# FlightComputer_RevA.net
KiCad netlist of a schematic drawn in EAGLE
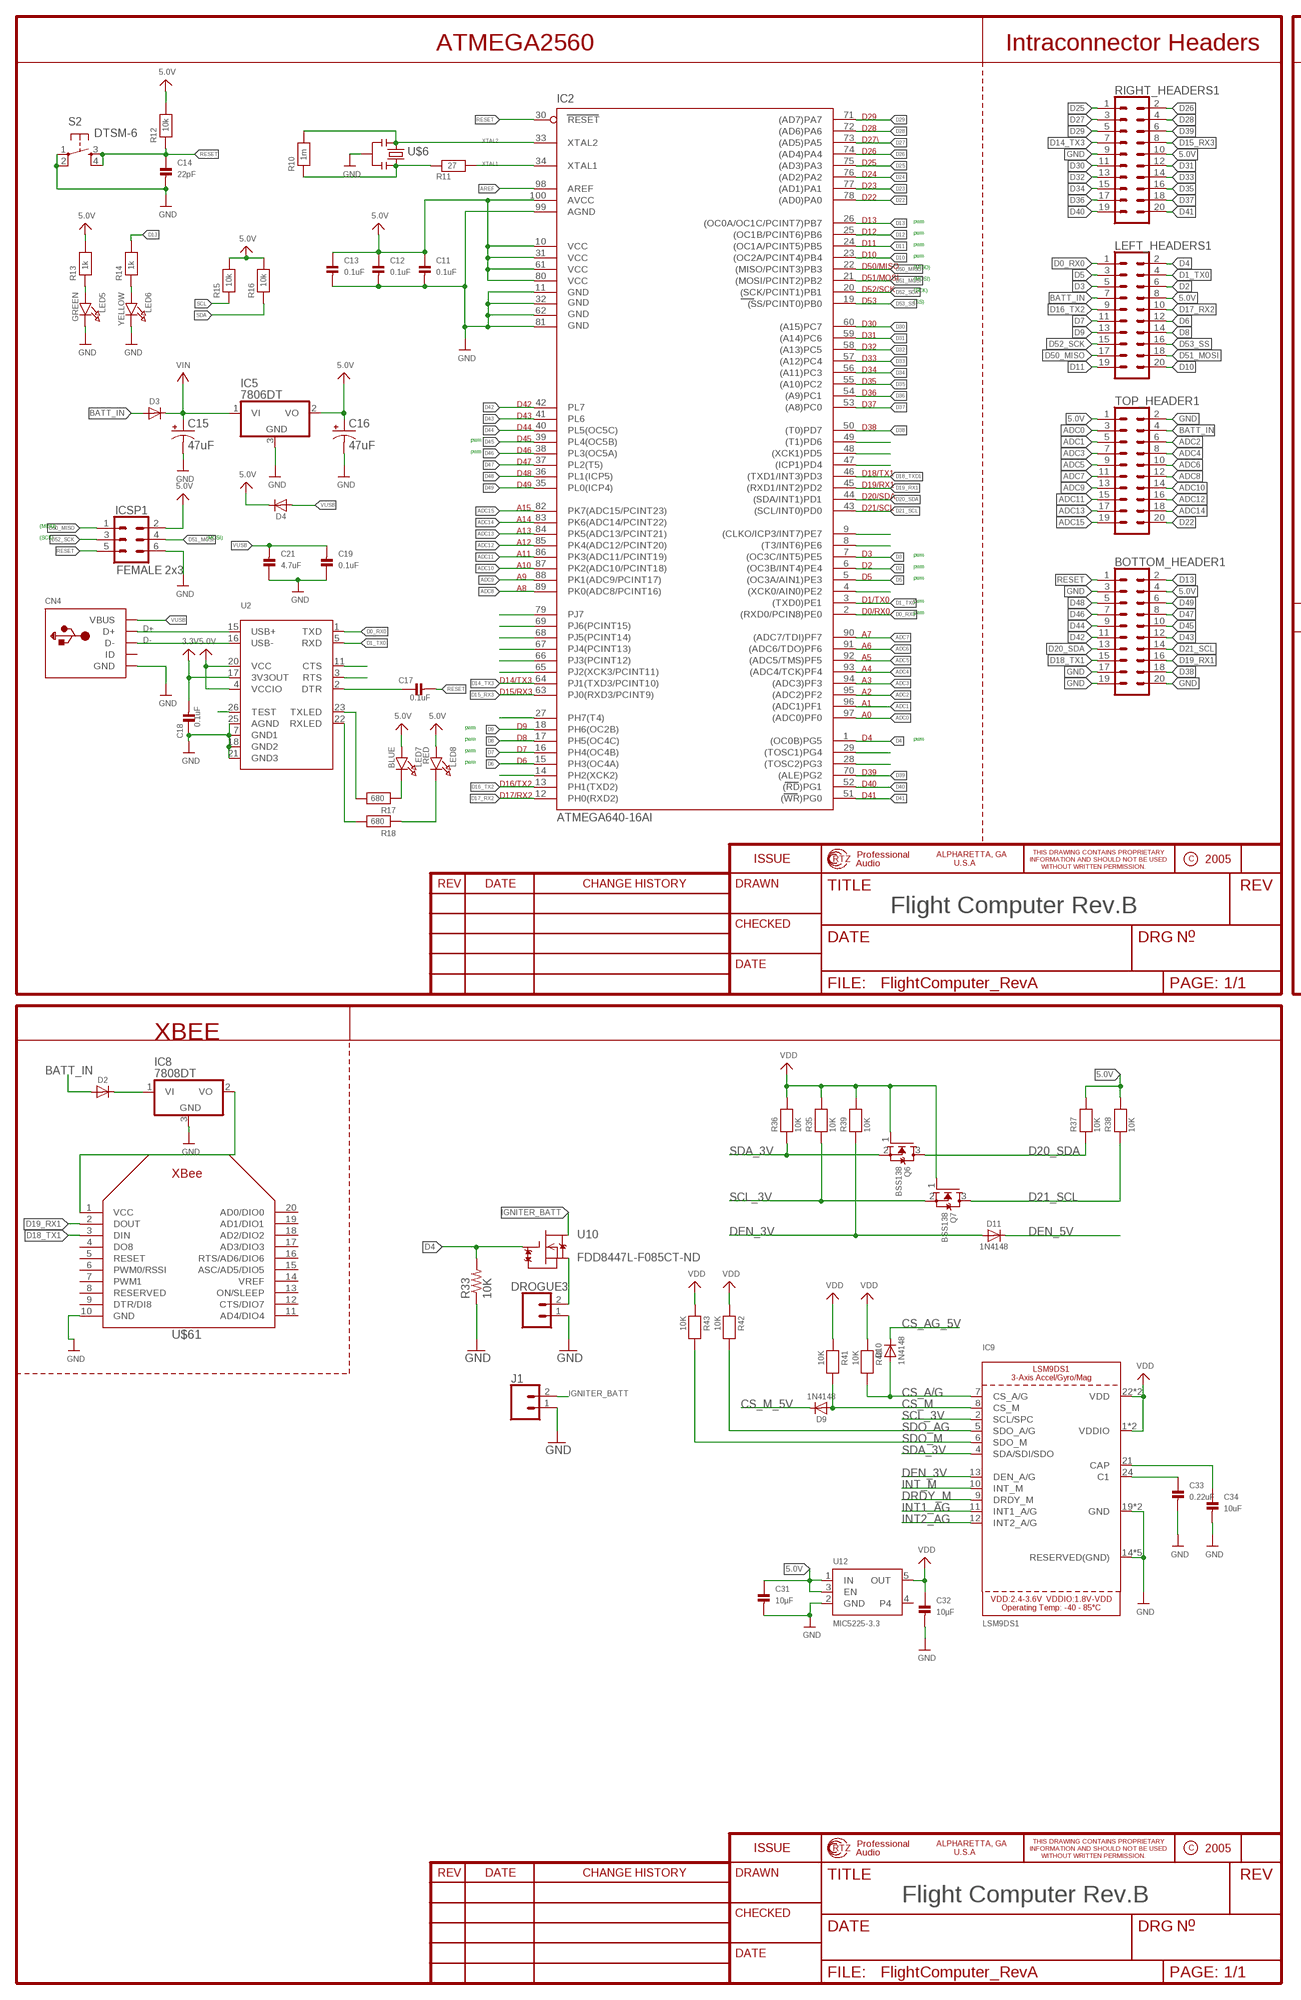
[diagram p0: schematic, sheet 1, part 1 of 2]
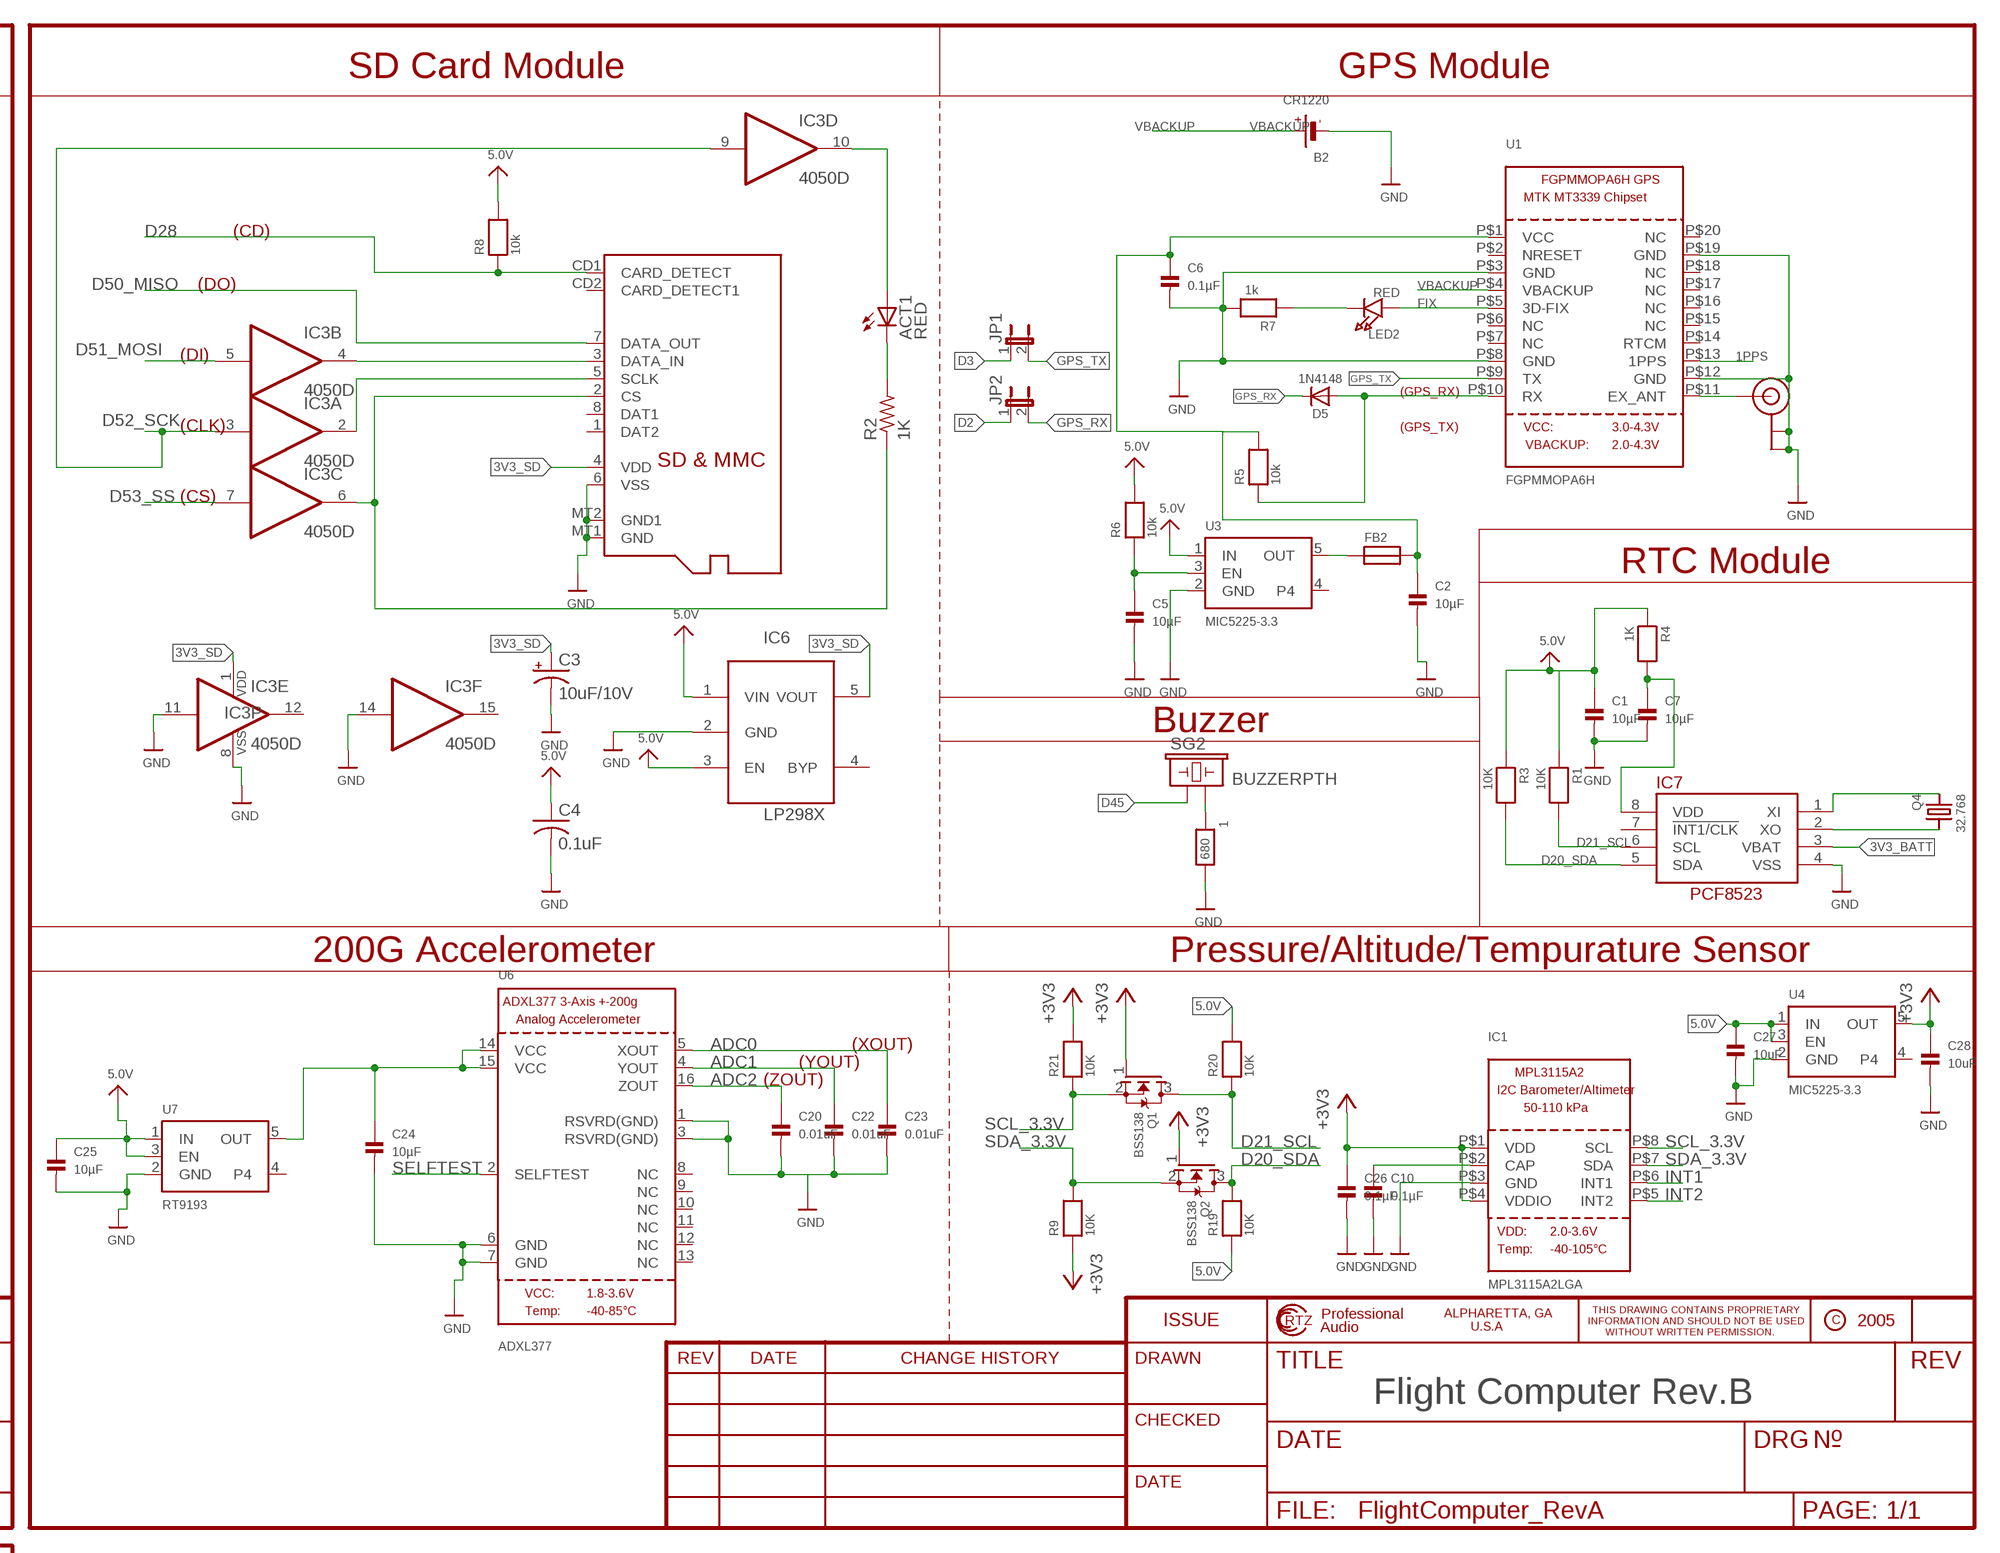
[diagram p1: schematic, sheet 1, part 2 of 2]

(export (version "E")
  (design (tool "Eeschema 10.0.6"))
  (components
    (comp (ref "1")
      (value "680")
      (footprint "eagle-import:0603")
      (libsource (lib "eagle-import") (part "RESISTOR0603"))
    )
    (comp (ref "ACT1")
      (value "RED")
      (footprint "eagle-import:CHIP-LED0805")
      (libsource (lib "eagle-import") (part "LEDCHIP-LED0805"))
    )
    (comp (ref "B2")
      (value "CR1220")
      (footprint "eagle-import:CR1220")
      (libsource (lib "eagle-import") (part "BATTERYCR1220_SMT"))
    )
    (comp (ref "BOTTOM_HEADER1")
      (value "CONN_10X2")
      (footprint "eagle-import:2X10")
      (libsource (lib "eagle-import") (part "CONN_10X2"))
    )
    (comp (ref "C1")
      (value "10µF")
      (footprint "eagle-import:0603")
      (libsource (lib "eagle-import") (part "CAP_CERAMIC0603"))
    )
    (comp (ref "C2")
      (value "10µF")
      (footprint "eagle-import:0603")
      (libsource (lib "eagle-import") (part "CAP_CERAMIC0603"))
    )
    (comp (ref "C3")
      (value "10uF/10V")
      (footprint "eagle-import:A_3216-18R")
      (libsource (lib "eagle-import") (part "CPOL-USA/3216-18R"))
    )
    (comp (ref "C4")
      (value "0.1uF")
      (footprint "eagle-import:C0805K")
      (libsource (lib "eagle-import") (part "C-USC0805K"))
    )
    (comp (ref "C5")
      (value "10µF")
      (footprint "eagle-import:0603")
      (libsource (lib "eagle-import") (part "CAP_CERAMIC0603"))
    )
    (comp (ref "C6")
      (value "0.1µF")
      (footprint "eagle-import:0603")
      (libsource (lib "eagle-import") (part "CAP_CERAMIC0603"))
    )
    (comp (ref "C7")
      (value "10µF")
      (footprint "eagle-import:0603")
      (libsource (lib "eagle-import") (part "CAP_CERAMIC0603"))
    )
    (comp (ref "C10")
      (value "0.1µF")
      (footprint "eagle-import:0603")
      (libsource (lib "eagle-import") (part "CAP_CERAMIC0603"))
    )
    (comp (ref "C11")
      (value "0.1uF")
      (footprint "eagle-import:0805")
      (libsource (lib "eagle-import") (part "CAP_CERAMIC0805"))
    )
    (comp (ref "C12")
      (value "0.1uF")
      (footprint "eagle-import:0805")
      (libsource (lib "eagle-import") (part "CAP_CERAMIC0805"))
    )
    (comp (ref "C13")
      (value "0.1uF")
      (footprint "eagle-import:0805")
      (libsource (lib "eagle-import") (part "CAP_CERAMIC0805"))
    )
    (comp (ref "C14")
      (value "22pF")
      (footprint "eagle-import:0805")
      (libsource (lib "eagle-import") (part "CAP_CERAMIC0805"))
    )
    (comp (ref "C15")
      (value "47uF")
      (footprint "eagle-import:PANASONIC_D")
      (libsource (lib "eagle-import") (part "rcl_334_CPOL-USD"))
    )
    (comp (ref "C16")
      (value "47uF")
      (footprint "eagle-import:PANASONIC_D")
      (libsource (lib "eagle-import") (part "rcl_334_CPOL-USD"))
    )
    (comp (ref "C17")
      (value "0.1uF")
      (footprint "eagle-import:0805")
      (libsource (lib "eagle-import") (part "CAP_CERAMIC0805"))
    )
    (comp (ref "C18")
      (value "0.1uF")
      (footprint "eagle-import:0805")
      (libsource (lib "eagle-import") (part "CAP_CERAMIC0805"))
    )
    (comp (ref "C19")
      (value "0.1uF")
      (footprint "eagle-import:0805")
      (libsource (lib "eagle-import") (part "CAP_CERAMIC0805"))
    )
    (comp (ref "C20")
      (value "0.01uF")
      (footprint "eagle-import:0603")
      (libsource (lib "eagle-import") (part "CAP_CERAMIC0603"))
    )
    (comp (ref "C21")
      (value "4.7uF")
      (footprint "eagle-import:0805")
      (libsource (lib "eagle-import") (part "CAP_CERAMIC0805"))
    )
    (comp (ref "C22")
      (value "0.01uF")
      (footprint "eagle-import:0603")
      (libsource (lib "eagle-import") (part "CAP_CERAMIC0603"))
    )
    (comp (ref "C23")
      (value "0.01uF")
      (footprint "eagle-import:0603")
      (libsource (lib "eagle-import") (part "CAP_CERAMIC0603"))
    )
    (comp (ref "C24")
      (value "10µF")
      (footprint "eagle-import:0603")
      (libsource (lib "eagle-import") (part "CAP_CERAMIC0603"))
    )
    (comp (ref "C25")
      (value "10µF")
      (footprint "eagle-import:0603")
      (libsource (lib "eagle-import") (part "CAP_CERAMIC0603"))
    )
    (comp (ref "C26")
      (value "0.1µF")
      (footprint "eagle-import:0603")
      (libsource (lib "eagle-import") (part "CAP_CERAMIC0603"))
    )
    (comp (ref "C27")
      (value "10uF")
      (footprint "eagle-import:0603")
      (libsource (lib "eagle-import") (part "CAP_CERAMIC0603"))
    )
    (comp (ref "C28")
      (value "10uF")
      (footprint "eagle-import:0603")
      (libsource (lib "eagle-import") (part "CAP_CERAMIC0603"))
    )
    (comp (ref "C31")
      (value "10µF")
      (footprint "eagle-import:0603")
      (libsource (lib "eagle-import") (part "CAP_CERAMIC0603"))
    )
    (comp (ref "C32")
      (value "10µF")
      (footprint "eagle-import:0603")
      (libsource (lib "eagle-import") (part "CAP_CERAMIC0603"))
    )
    (comp (ref "C33")
      (value "0.22uF")
      (footprint "eagle-import:0603")
      (libsource (lib "eagle-import") (part "CAP_CERAMIC0603"))
    )
    (comp (ref "C34")
      (value "10uF")
      (footprint "eagle-import:0603")
      (libsource (lib "eagle-import") (part "CAP_CERAMIC0603"))
    )
    (comp (ref "CN4")
      (value "USBMINIB")
      (footprint "eagle-import:USB-MINIB")
      (libsource (lib "eagle-import") (part "USBMINIB"))
    )
    (comp (ref "D2")
      (value "DIODESOD-123")
      (footprint "eagle-import:SOD-123")
      (libsource (lib "eagle-import") (part "DIODESOD-123"))
    )
    (comp (ref "D3")
      (value "DIODESOD-123")
      (footprint "eagle-import:SOD-123")
      (libsource (lib "eagle-import") (part "DIODESOD-123"))
    )
    (comp (ref "D4")
      (value "DIODESOD-123")
      (footprint "eagle-import:SOD-123")
      (libsource (lib "eagle-import") (part "DIODESOD-123"))
    )
    (comp (ref "D5")
      (value "1N4148")
      (footprint "eagle-import:SOD-323")
      (libsource (lib "eagle-import") (part "DIODESOD-323"))
    )
    (comp (ref "D9")
      (value "1N4148")
      (footprint "eagle-import:SOD-323")
      (libsource (lib "eagle-import") (part "DIODESOD-323"))
    )
    (comp (ref "D10")
      (value "1N4148")
      (footprint "eagle-import:SOD-323")
      (libsource (lib "eagle-import") (part "DIODESOD-323"))
    )
    (comp (ref "D11")
      (value "1N4148")
      (footprint "eagle-import:SOD-323")
      (libsource (lib "eagle-import") (part "DIODESOD-323"))
    )
    (comp (ref "DROGUE3")
      (value "CONN_023.5MM")
      (footprint "eagle-import:SCREWTERMINAL-3.5MM-2")
      (libsource (lib "eagle-import") (part "CONN_023.5MM"))
    )
    (comp (ref "FB2")
      (value "FERRITE")
      (footprint "eagle-import:0603")
      (libsource (lib "eagle-import") (part "FERRITE"))
    )
    (comp (ref "IC1")
      (value "MPL3115A2LGA")
      (footprint "eagle-import:LGA8")
      (libsource (lib "eagle-import") (part "MPL3115A2LGA"))
    )
    (comp (ref "IC2")
      (value "ATMEGA640-16AI")
      (footprint "eagle-import:TQFP100")
      (libsource (lib "eagle-import") (part "ATMEGAAI640-16"))
    )
    (comp (ref "IC3")
      (value "4050D")
      (footprint "eagle-import:SO16")
      (libsource (lib "eagle-import") (part "4050D"))
    )
    (comp (ref "IC5")
      (value "7806DT")
      (footprint "eagle-import:TO252")
      (libsource (lib "eagle-import") (part "78DT06"))
    )
    (comp (ref "IC6")
      (value "LP298XS")
      (footprint "eagle-import:SOT23-5L")
      (libsource (lib "eagle-import") (part "LP298XS"))
    )
    (comp (ref "IC7")
      (value "RTC_PCF8523T")
      (footprint "eagle-import:SOIC8_150MIL")
      (libsource (lib "eagle-import") (part "RTC_PCF8523T"))
    )
    (comp (ref "IC8")
      (value "7808DT")
      (footprint "eagle-import:TO252")
      (libsource (lib "eagle-import") (part "78DT08"))
    )
    (comp (ref "IC9")
      (value "LSM9DS1")
      (footprint "eagle-import:LGA24_3.5X3.1MM")
      (libsource (lib "eagle-import") (part "LSM9DS1"))
    )
    (comp (ref "ICSP1")
      (value "FEMALE 2x3")
      (footprint "eagle-import:2X3")
      (libsource (lib "eagle-import") (part "CONN_03X2FEMALE"))
    )
    (comp (ref "J1")
      (value "CONN_02")
      (footprint "eagle-import:1X02")
      (libsource (lib "eagle-import") (part "CONN_02"))
    )
    (comp (ref "JP1")
      (value "JUMPER-2SMD-NO-NS")
      (footprint "eagle-import:SJ_2S-NO-NS")
      (libsource (lib "eagle-import") (part "JUMPER-2SMD-NO-NS"))
    )
    (comp (ref "JP2")
      (value "JUMPER-2SMD-NO-NS")
      (footprint "eagle-import:SJ_2S-NO-NS")
      (libsource (lib "eagle-import") (part "JUMPER-2SMD-NO-NS"))
    )
    (comp (ref "LED2")
      (value "RED")
      (footprint "eagle-import:CHIPLED_0805")
      (libsource (lib "eagle-import") (part "LED0805"))
    )
    (comp (ref "LED5")
      (value "GREEN")
      (footprint "eagle-import:CHIPLED_0805")
      (libsource (lib "eagle-import") (part "LED0805"))
    )
    (comp (ref "LED6")
      (value "YELLOW")
      (footprint "eagle-import:CHIPLED_0805")
      (libsource (lib "eagle-import") (part "LED0805"))
    )
    (comp (ref "LED7")
      (value "BLUE")
      (footprint "eagle-import:CHIPLED_0805")
      (libsource (lib "eagle-import") (part "LED0805"))
    )
    (comp (ref "LED8")
      (value "RED")
      (footprint "eagle-import:CHIPLED_0805")
      (libsource (lib "eagle-import") (part "LED0805"))
    )
    (comp (ref "LEFT_HEADERS1")
      (value "CONN_10X2")
      (footprint "eagle-import:2X10")
      (libsource (lib "eagle-import") (part "CONN_10X2"))
    )
    (comp (ref "Q1")
      (value "BSS138")
      (footprint "eagle-import:SOT23-WIDE")
      (libsource (lib "eagle-import") (part "MOSFET-NWIDE"))
    )
    (comp (ref "Q2")
      (value "BSS138")
      (footprint "eagle-import:SOT23-WIDE")
      (libsource (lib "eagle-import") (part "MOSFET-NWIDE"))
    )
    (comp (ref "Q4")
      (value "32.768")
      (footprint "eagle-import:CRYSTAL_8X3.8")
      (libsource (lib "eagle-import") (part "CRYSTAL8.0X3.8"))
    )
    (comp (ref "Q6")
      (value "BSS138")
      (footprint "eagle-import:SOT23-WIDE")
      (libsource (lib "eagle-import") (part "MOSFET-NWIDE"))
    )
    (comp (ref "Q7")
      (value "BSS138")
      (footprint "eagle-import:SOT23-WIDE")
      (libsource (lib "eagle-import") (part "MOSFET-NWIDE"))
    )
    (comp (ref "R1")
      (value "10K")
      (footprint "eagle-import:0603")
      (libsource (lib "eagle-import") (part "RESISTOR0603"))
    )
    (comp (ref "R2")
      (value "1K")
      (footprint "eagle-import:R0805")
      (libsource (lib "eagle-import") (part "R-US_R0805"))
    )
    (comp (ref "R3")
      (value "10K")
      (footprint "eagle-import:0603")
      (libsource (lib "eagle-import") (part "RESISTOR0603"))
    )
    (comp (ref "R4")
      (value "1K")
      (footprint "eagle-import:0603")
      (libsource (lib "eagle-import") (part "RESISTOR0603"))
    )
    (comp (ref "R5")
      (value "10k")
      (footprint "eagle-import:0603")
      (libsource (lib "eagle-import") (part "RESISTOR0603"))
    )
    (comp (ref "R6")
      (value "10k")
      (footprint "eagle-import:0603")
      (libsource (lib "eagle-import") (part "RESISTOR0603"))
    )
    (comp (ref "R7")
      (value "1k")
      (footprint "eagle-import:0603")
      (libsource (lib "eagle-import") (part "RESISTOR0603"))
    )
    (comp (ref "R8")
      (value "10k")
      (footprint "eagle-import:0603")
      (libsource (lib "eagle-import") (part "RESISTOR0603"))
    )
    (comp (ref "R9")
      (value "10K")
      (footprint "eagle-import:0603")
      (libsource (lib "eagle-import") (part "RESISTOR0603"))
    )
    (comp (ref "R10")
      (value "1m")
      (footprint "eagle-import:0805")
      (libsource (lib "eagle-import") (part "RESISTOR0805"))
    )
    (comp (ref "R11")
      (value "27")
      (footprint "eagle-import:0805")
      (libsource (lib "eagle-import") (part "RESISTOR0805"))
    )
    (comp (ref "R12")
      (value "10k")
      (footprint "eagle-import:0805")
      (libsource (lib "eagle-import") (part "RESISTOR0805"))
    )
    (comp (ref "R13")
      (value "1k")
      (footprint "eagle-import:0805")
      (libsource (lib "eagle-import") (part "RESISTOR0805"))
    )
    (comp (ref "R14")
      (value "1k")
      (footprint "eagle-import:0805")
      (libsource (lib "eagle-import") (part "RESISTOR0805"))
    )
    (comp (ref "R15")
      (value "10k")
      (footprint "eagle-import:0805")
      (libsource (lib "eagle-import") (part "RESISTOR0805"))
    )
    (comp (ref "R16")
      (value "10k")
      (footprint "eagle-import:0805")
      (libsource (lib "eagle-import") (part "RESISTOR0805"))
    )
    (comp (ref "R17")
      (value "680")
      (footprint "eagle-import:0805")
      (libsource (lib "eagle-import") (part "RESISTOR0805"))
    )
    (comp (ref "R18")
      (value "680")
      (footprint "eagle-import:0805")
      (libsource (lib "eagle-import") (part "RESISTOR0805"))
    )
    (comp (ref "R19")
      (value "10K")
      (footprint "eagle-import:0603")
      (libsource (lib "eagle-import") (part "RESISTOR0603"))
    )
    (comp (ref "R20")
      (value "10K")
      (footprint "eagle-import:0603")
      (libsource (lib "eagle-import") (part "RESISTOR0603"))
    )
    (comp (ref "R21")
      (value "10K")
      (footprint "eagle-import:0603")
      (libsource (lib "eagle-import") (part "RESISTOR0603"))
    )
    (comp (ref "R33")
      (value "10K")
      (footprint "eagle-import:R0805")
      (libsource (lib "eagle-import") (part "R-US_R0805"))
    )
    (comp (ref "R35")
      (value "10K")
      (footprint "eagle-import:0603")
      (libsource (lib "eagle-import") (part "RESISTOR0603"))
    )
    (comp (ref "R36")
      (value "10K")
      (footprint "eagle-import:0603")
      (libsource (lib "eagle-import") (part "RESISTOR0603"))
    )
    (comp (ref "R37")
      (value "10K")
      (footprint "eagle-import:0603")
      (libsource (lib "eagle-import") (part "RESISTOR0603"))
    )
    (comp (ref "R38")
      (value "10K")
      (footprint "eagle-import:0603")
      (libsource (lib "eagle-import") (part "RESISTOR0603"))
    )
    (comp (ref "R39")
      (value "10K")
      (footprint "eagle-import:0603")
      (libsource (lib "eagle-import") (part "RESISTOR0603"))
    )
    (comp (ref "R40")
      (value "10K")
      (footprint "eagle-import:0603")
      (libsource (lib "eagle-import") (part "RESISTOR0603"))
    )
    (comp (ref "R41")
      (value "10K")
      (footprint "eagle-import:0603")
      (libsource (lib "eagle-import") (part "RESISTOR0603"))
    )
    (comp (ref "R42")
      (value "10K")
      (footprint "eagle-import:0603")
      (libsource (lib "eagle-import") (part "RESISTOR0603"))
    )
    (comp (ref "R43")
      (value "10K")
      (footprint "eagle-import:0603")
      (libsource (lib "eagle-import") (part "RESISTOR0603"))
    )
    (comp (ref "RIGHT_HEADERS1")
      (value "CONN_10X2")
      (footprint "eagle-import:2X10")
      (libsource (lib "eagle-import") (part "CONN_10X2"))
    )
    (comp (ref "S2")
      (value "DTSM-6")
      (footprint "eagle-import:DTSM-6")
      (libsource (lib "eagle-import") (part "DTSM-6"))
    )
    (comp (ref "SG2")
      (value "BUZZERPTH")
      (footprint "eagle-import:BUZZER-12MM")
      (libsource (lib "eagle-import") (part "BUZZERPTH"))
    )
    (comp (ref "TOP_HEADER1")
      (value "CONN_10X2")
      (footprint "eagle-import:2X10")
      (libsource (lib "eagle-import") (part "CONN_10X2"))
    )
    (comp (ref "U$1")
      (value "U.FL")
      (footprint "eagle-import:U.FL")
      (libsource (lib "eagle-import") (part "U.FL"))
    )
    (comp (ref "U$6")
      (value "RESONATORSMD")
      (footprint "eagle-import:RESONATOR-SMD")
      (libsource (lib "eagle-import") (part "RESONATORSMD"))
    )
    (comp (ref "U$61")
      (value "XBEE")
      (footprint "eagle-import:XBEE")
      (libsource (lib "eagle-import") (part "XBEE"))
    )
    (comp (ref "U1")
      (value "FGPMMOPA6H")
      (footprint "eagle-import:FGPMMOPA6H")
      (libsource (lib "eagle-import") (part "GPS_FGPMMOPA6H"))
    )
    (comp (ref "U2")
      (value "FT232RLSSOP28")
      (footprint "eagle-import:SSOP28DB")
      (libsource (lib "eagle-import") (part "FT232RLSSOP28"))
    )
    (comp (ref "U3")
      (value "MIC5225-3.3")
      (footprint "eagle-import:SOT23-5")
      (libsource (lib "eagle-import") (part "VREG_SOT23-5"))
    )
    (comp (ref "U4")
      (value "MIC5225-3.3")
      (footprint "eagle-import:SOT23-5")
      (libsource (lib "eagle-import") (part "VREG_SOT23-5"))
    )
    (comp (ref "U6")
      (value "ADXL377")
      (footprint "eagle-import:LFCSP16_LQ")
      (libsource (lib "eagle-import") (part "ACCEL_ADXL377"))
    )
    (comp (ref "U7")
      (value "RT9193")
      (footprint "eagle-import:SOT23-5")
      (libsource (lib "eagle-import") (part "VREG_SOT23-5"))
    )
    (comp (ref "U10")
      (value "FDD8447L-F085CT-ND")
      (footprint "eagle-import:TO252")
      (libsource (lib "eagle-import") (part "TSM4ND50"))
    )
    (comp (ref "U12")
      (value "MIC5225-3.3")
      (footprint "eagle-import:SOT23-5")
      (libsource (lib "eagle-import") (part "VREG_SOT23-5"))
    )
    (comp (ref "X2")
      (value "MICROSD")
      (footprint "eagle-import:MICROSD")
      (libsource (lib "eagle-import") (part "MICROSD"))
    )
  )
  (nets
    (net (code "1") (name "+3V3") (class "Default")
      (node (ref "C26") (pin "1") (pinfunction "P$1_1") (pintype "passive"))
      (node (ref "C28") (pin "1") (pinfunction "P$1_1") (pintype "passive"))
      (node (ref "IC1") (pin "P$1") (pinfunction "VDD_P$1") (pintype "power_in"))
      (node (ref "IC1") (pin "P$4") (pinfunction "VDDIO_P$4") (pintype "power_in"))
      (node (ref "Q1") (pin "1") (pinfunction "G_1") (pintype "bidirectional"))
      (node (ref "Q2") (pin "1") (pinfunction "G_1") (pintype "bidirectional"))
      (node (ref "R21") (pin "2") (pinfunction "2_2") (pintype "passive"))
      (node (ref "R9") (pin "1") (pinfunction "1_1") (pintype "passive"))
      (node (ref "U4") (pin "5") (pinfunction "OUT_5") (pintype "power_in"))
    )
    (net (code "2") (name "/1PPS") (class "Default")
      (node (ref "U1") (pin "P$13") (pinfunction "1PPS_P$13") (pintype "bidirectional"))
    )
    (net (code "3") (name "/CS_AG_5V") (class "Default")
      (node (ref "D10") (pin "C") (pinfunction "C_C") (pintype "passive"))
    )
    (net (code "4") (name "/CS_A{slash}G") (class "Default")
      (node (ref "D10") (pin "A") (pinfunction "A_A") (pintype "passive"))
      (node (ref "IC9") (pin "7") (pinfunction "CS_A/G_7") (pintype "bidirectional"))
      (node (ref "R40") (pin "2") (pinfunction "2_2") (pintype "passive"))
    )
    (net (code "5") (name "/CS_M") (class "Default")
      (node (ref "D9") (pin "A") (pinfunction "A_A") (pintype "passive"))
      (node (ref "IC9") (pin "8") (pinfunction "CS_M_8") (pintype "bidirectional"))
      (node (ref "R41") (pin "2") (pinfunction "2_2") (pintype "passive"))
    )
    (net (code "6") (name "/CS_M_5V") (class "Default")
      (node (ref "D9") (pin "C") (pinfunction "C_C") (pintype "passive"))
    )
    (net (code "7") (name "/D+") (class "Default")
      (node (ref "CN4") (pin "D+") (pinfunction "D+_D+") (pintype "bidirectional"))
      (node (ref "U2") (pin "15") (pinfunction "USB+_15") (pintype "bidirectional"))
    )
    (net (code "8") (name "/D-") (class "Default")
      (node (ref "CN4") (pin "D-") (pinfunction "D-_D-") (pintype "bidirectional"))
      (node (ref "U2") (pin "16") (pinfunction "USB-_16") (pintype "bidirectional"))
    )
    (net (code "9") (name "/DEN_3V") (class "Default")
      (node (ref "D11") (pin "A") (pinfunction "A_A") (pintype "passive"))
      (node (ref "IC9") (pin "13") (pinfunction "DEN_A/G_13") (pintype "bidirectional"))
      (node (ref "R39") (pin "1") (pinfunction "1_1") (pintype "passive"))
    )
    (net (code "10") (name "/DEN_5V") (class "Default")
      (node (ref "D11") (pin "C") (pinfunction "C_C") (pintype "passive"))
    )
    (net (code "11") (name "/DRDY_M") (class "Default")
      (node (ref "IC9") (pin "9") (pinfunction "DRDY_M_9") (pintype "bidirectional"))
    )
    (net (code "12") (name "/FIX") (class "Default")
      (node (ref "LED2") (pin "A") (pinfunction "A_A") (pintype "passive"))
      (node (ref "U1") (pin "P$5") (pinfunction "3D-FIX_P$5") (pintype "bidirectional"))
    )
    (net (code "13") (name "/INT1") (class "Default")
      (node (ref "IC1") (pin "P$6") (pinfunction "INT1_P$6") (pintype "output"))
    )
    (net (code "14") (name "/INT1_AG") (class "Default")
      (node (ref "IC9") (pin "11") (pinfunction "INT1_A/G_11") (pintype "bidirectional"))
    )
    (net (code "15") (name "/INT2") (class "Default")
      (node (ref "IC1") (pin "P$5") (pinfunction "INT2_P$5") (pintype "output"))
    )
    (net (code "16") (name "/INT2_AG") (class "Default")
      (node (ref "IC9") (pin "12") (pinfunction "INT2_A/G_12") (pintype "bidirectional"))
    )
    (net (code "17") (name "/INT_M") (class "Default")
      (node (ref "IC9") (pin "10") (pinfunction "INT_M_10") (pintype "bidirectional"))
    )
    (net (code "18") (name "/N$36") (class "Default")
      (node (ref "C24") (pin "1") (pinfunction "P$1_1") (pintype "passive"))
      (node (ref "IC2") (pin "14") (pinfunction "PH2(XCK2)_14") (pintype "bidirectional"))
      (node (ref "U6") (pin "14") (pinfunction "VCC_14") (pintype "power_in"))
      (node (ref "U6") (pin "15") (pinfunction "VCC_15") (pintype "power_in"))
      (node (ref "U7") (pin "5") (pinfunction "OUT_5") (pintype "power_in"))
    )
    (net (code "19") (name "/SCL_3.3V") (class "Default")
      (node (ref "IC1") (pin "P$8") (pinfunction "SCL_P$8") (pintype "bidirectional"))
      (node (ref "Q1") (pin "2") (pinfunction "S_2") (pintype "bidirectional"))
      (node (ref "R21") (pin "1") (pinfunction "1_1") (pintype "passive"))
    )
    (net (code "20") (name "/SCL_3V") (class "Default")
      (node (ref "IC9") (pin "2") (pinfunction "SCL/SPC_2") (pintype "bidirectional"))
      (node (ref "Q7") (pin "2") (pinfunction "S_2") (pintype "bidirectional"))
      (node (ref "R35") (pin "1") (pinfunction "1_1") (pintype "passive"))
    )
    (net (code "21") (name "/SDA_3.3V") (class "Default")
      (node (ref "IC1") (pin "P$7") (pinfunction "SDA_P$7") (pintype "bidirectional"))
      (node (ref "Q2") (pin "2") (pinfunction "S_2") (pintype "bidirectional"))
      (node (ref "R9") (pin "2") (pinfunction "2_2") (pintype "passive"))
    )
    (net (code "22") (name "/SDA_3V") (class "Default")
      (node (ref "IC9") (pin "4") (pinfunction "SDA/SDI/SDO_4") (pintype "bidirectional"))
      (node (ref "Q6") (pin "2") (pinfunction "S_2") (pintype "bidirectional"))
      (node (ref "R36") (pin "1") (pinfunction "1_1") (pintype "passive"))
    )
    (net (code "23") (name "/SDO_AG") (class "Default")
      (node (ref "IC9") (pin "5") (pinfunction "SDO_A/G_5") (pintype "bidirectional"))
      (node (ref "R42") (pin "2") (pinfunction "2_2") (pintype "passive"))
    )
    (net (code "24") (name "/SDO_M") (class "Default")
      (node (ref "IC9") (pin "6") (pinfunction "SDO_M_6") (pintype "bidirectional"))
      (node (ref "R43") (pin "2") (pinfunction "2_2") (pintype "passive"))
    )
    (net (code "25") (name "/SELFTEST") (class "Default")
      (node (ref "U6") (pin "2") (pinfunction "SELFTEST_2") (pintype "bidirectional"))
    )
    (net (code "26") (name "/VBACKUP") (class "Default")
      (node (ref "B2") (pin "+$1") (pinfunction "+_+$1") (pintype "passive"))
      (node (ref "B2") (pin "+$2") (pinfunction "+_+$2") (pintype "passive"))
      (node (ref "U1") (pin "P$4") (pinfunction "VBACKUP_P$4") (pintype "bidirectional"))
    )
    (net (code "27") (name "/XTAL1") (class "Default")
      (node (ref "IC2") (pin "34") (pinfunction "XTAL1_34") (pintype "input"))
      (node (ref "R11") (pin "1") (pinfunction "1_1") (pintype "passive"))
    )
    (net (code "28") (name "/XTAL2") (class "Default")
      (node (ref "IC2") (pin "33") (pinfunction "XTAL2_33") (pintype "output"))
      (node (ref "R10") (pin "2") (pinfunction "2_2") (pintype "passive"))
      (node (ref "U$6") (pin "1") (pinfunction "1_1") (pintype "passive"))
    )
    (net (code "29") (name "3.3V") (class "Default")
      (node (ref "C18") (pin "2") (pinfunction "P$2_2") (pintype "passive"))
      (node (ref "U2") (pin "17") (pinfunction "3V3OUT_17") (pintype "power_in"))
    )
    (net (code "30") (name "3V3_BATT") (class "Default")
      (node (ref "IC7") (pin "3") (pinfunction "VBAT_3") (pintype "power_in"))
    )
    (net (code "31") (name "3V3_SD") (class "Default")
      (node (ref "C3") (pin "+") (pinfunction "+_+") (pintype "passive"))
      (node (ref "IC3") (pin "1") (pinfunction "VDD_1") (pintype "power_in"))
      (node (ref "IC6") (pin "5") (pinfunction "VOUT_5") (pintype "bidirectional"))
      (node (ref "X2") (pin "4") (pinfunction "VDD_4") (pintype "power_in"))
    )
    (net (code "32") (name "5.0V") (class "Default")
      (node (ref "BOTTOM_HEADER1") (pin "4") (pinfunction "4_4") (pintype "passive"))
      (node (ref "C1") (pin "1") (pinfunction "P$1_1") (pintype "passive"))
      (node (ref "C11") (pin "1") (pinfunction "P$1_1") (pintype "passive"))
      (node (ref "C12") (pin "1") (pinfunction "P$1_1") (pintype "passive"))
      (node (ref "C13") (pin "1") (pinfunction "P$1_1") (pintype "passive"))
      (node (ref "C16") (pin "+") (pinfunction "+_+") (pintype "passive"))
      (node (ref "C25") (pin "1") (pinfunction "P$1_1") (pintype "passive"))
      (node (ref "C27") (pin "1") (pinfunction "P$1_1") (pintype "passive"))
      (node (ref "C31") (pin "1") (pinfunction "P$1_1") (pintype "passive"))
      (node (ref "C4") (pin "1") (pinfunction "1_1") (pintype "passive"))
      (node (ref "D4") (pin "C") (pinfunction "C_C") (pintype "passive"))
      (node (ref "IC2") (pin "10") (pinfunction "VCC_10") (pintype "power_in"))
      (node (ref "IC2") (pin "100") (pinfunction "AVCC_100") (pintype "power_in"))
      (node (ref "IC2") (pin "31") (pinfunction "VCC1_31") (pintype "power_in"))
      (node (ref "IC2") (pin "61") (pinfunction "VCC2_61") (pintype "power_in"))
      (node (ref "IC2") (pin "80") (pinfunction "VCC3_80") (pintype "power_in"))
      (node (ref "IC5") (pin "2") (pinfunction "VO_2") (pintype "passive"))
      (node (ref "IC6") (pin "1") (pinfunction "VIN_1") (pintype "bidirectional"))
      (node (ref "IC6") (pin "3") (pinfunction "EN_3") (pintype "bidirectional"))
      (node (ref "ICSP1") (pin "2") (pinfunction "2_2") (pintype "bidirectional"))
      (node (ref "LED7") (pin "A") (pinfunction "A_A") (pintype "passive"))
      (node (ref "LED8") (pin "A") (pinfunction "A_A") (pintype "passive"))
      (node (ref "LEFT_HEADERS1") (pin "8") (pinfunction "8_8") (pintype "passive"))
      (node (ref "R1") (pin "1") (pinfunction "1_1") (pintype "passive"))
      (node (ref "R12") (pin "2") (pinfunction "2_2") (pintype "passive"))
      (node (ref "R13") (pin "2") (pinfunction "2_2") (pintype "passive"))
      (node (ref "R15") (pin "2") (pinfunction "2_2") (pintype "passive"))
      (node (ref "R16") (pin "2") (pinfunction "2_2") (pintype "passive"))
      (node (ref "R19") (pin "1") (pinfunction "1_1") (pintype "passive"))
      (node (ref "R20") (pin "2") (pinfunction "2_2") (pintype "passive"))
      (node (ref "R3") (pin "1") (pinfunction "1_1") (pintype "passive"))
      (node (ref "R37") (pin "2") (pinfunction "2_2") (pintype "passive"))
      (node (ref "R38") (pin "2") (pinfunction "2_2") (pintype "passive"))
      (node (ref "R4") (pin "1") (pinfunction "1_1") (pintype "passive"))
      (node (ref "R6") (pin "2") (pinfunction "2_2") (pintype "passive"))
      (node (ref "R8") (pin "2") (pinfunction "2_2") (pintype "passive"))
      (node (ref "RIGHT_HEADERS1") (pin "10") (pinfunction "10_10") (pintype "passive"))
      (node (ref "TOP_HEADER1") (pin "1") (pinfunction "1_1") (pintype "passive"))
      (node (ref "U12") (pin "1") (pinfunction "IN_1") (pintype "power_in"))
      (node (ref "U12") (pin "3") (pinfunction "EN_3") (pintype "input"))
      (node (ref "U2") (pin "20") (pinfunction "VCC_20") (pintype "power_in"))
      (node (ref "U2") (pin "4") (pinfunction "VCCIO_4") (pintype "power_in"))
      (node (ref "U3") (pin "1") (pinfunction "IN_1") (pintype "power_in"))
      (node (ref "U4") (pin "1") (pinfunction "IN_1") (pintype "power_in"))
      (node (ref "U4") (pin "3") (pinfunction "EN_3") (pintype "input"))
      (node (ref "U7") (pin "1") (pinfunction "IN_1") (pintype "power_in"))
      (node (ref "U7") (pin "3") (pinfunction "EN_3") (pintype "input"))
    )
    (net (code "33") (name "ADC0") (class "Default")
      (node (ref "C23") (pin "1") (pinfunction "P$1_1") (pintype "passive"))
      (node (ref "IC2") (pin "97") (pinfunction "(ADC0)PF0_97") (pintype "bidirectional"))
      (node (ref "TOP_HEADER1") (pin "3") (pinfunction "3_3") (pintype "passive"))
      (node (ref "U6") (pin "5") (pinfunction "XOUT_5") (pintype "output"))
    )
    (net (code "34") (name "ADC1") (class "Default")
      (node (ref "C22") (pin "1") (pinfunction "P$1_1") (pintype "passive"))
      (node (ref "IC2") (pin "96") (pinfunction "(ADC1)PF1_96") (pintype "bidirectional"))
      (node (ref "TOP_HEADER1") (pin "5") (pinfunction "5_5") (pintype "passive"))
      (node (ref "U6") (pin "4") (pinfunction "YOUT_4") (pintype "output"))
    )
    (net (code "35") (name "ADC2") (class "Default")
      (node (ref "C20") (pin "1") (pinfunction "P$1_1") (pintype "passive"))
      (node (ref "IC2") (pin "95") (pinfunction "(ADC2)PF2_95") (pintype "bidirectional"))
      (node (ref "TOP_HEADER1") (pin "6") (pinfunction "6_6") (pintype "passive"))
      (node (ref "U6") (pin "16") (pinfunction "ZOUT_16") (pintype "output"))
    )
    (net (code "36") (name "ADC3") (class "Default")
      (node (ref "IC2") (pin "94") (pinfunction "(ADC3)PF3_94") (pintype "bidirectional"))
      (node (ref "TOP_HEADER1") (pin "7") (pinfunction "7_7") (pintype "passive"))
    )
    (net (code "37") (name "ADC4") (class "Default")
      (node (ref "IC2") (pin "93") (pinfunction "(ADC4/TCK)PF4_93") (pintype "bidirectional"))
      (node (ref "TOP_HEADER1") (pin "8") (pinfunction "8_8") (pintype "passive"))
    )
    (net (code "38") (name "ADC5") (class "Default")
      (node (ref "IC2") (pin "92") (pinfunction "(ADC5/TMS)PF5_92") (pintype "bidirectional"))
      (node (ref "TOP_HEADER1") (pin "9") (pinfunction "9_9") (pintype "passive"))
    )
    (net (code "39") (name "ADC6") (class "Default")
      (node (ref "IC2") (pin "91") (pinfunction "(ADC6/TDO)PF6_91") (pintype "bidirectional"))
      (node (ref "TOP_HEADER1") (pin "10") (pinfunction "10_10") (pintype "passive"))
    )
    (net (code "40") (name "ADC7") (class "Default")
      (node (ref "IC2") (pin "90") (pinfunction "(ADC7/TDI)PF7_90") (pintype "bidirectional"))
      (node (ref "TOP_HEADER1") (pin "11") (pinfunction "11_11") (pintype "passive"))
    )
    (net (code "41") (name "ADC8") (class "Default")
      (node (ref "IC2") (pin "89") (pinfunction "PK0(ADC8/PCINT16)_89") (pintype "bidirectional"))
      (node (ref "TOP_HEADER1") (pin "12") (pinfunction "12_12") (pintype "passive"))
    )
    (net (code "42") (name "ADC9") (class "Default")
      (node (ref "IC2") (pin "88") (pinfunction "PK1(ADC9/PCINT17)_88") (pintype "bidirectional"))
      (node (ref "TOP_HEADER1") (pin "13") (pinfunction "13_13") (pintype "passive"))
    )
    (net (code "43") (name "ADC10") (class "Default")
      (node (ref "IC2") (pin "87") (pinfunction "PK2(ADC10/PCINT18)_87") (pintype "bidirectional"))
      (node (ref "TOP_HEADER1") (pin "14") (pinfunction "14_14") (pintype "passive"))
    )
    (net (code "44") (name "ADC11") (class "Default")
      (node (ref "IC2") (pin "86") (pinfunction "PK3(ADC11/PCINT19)_86") (pintype "bidirectional"))
      (node (ref "TOP_HEADER1") (pin "15") (pinfunction "15_15") (pintype "passive"))
    )
    (net (code "45") (name "ADC12") (class "Default")
      (node (ref "IC2") (pin "85") (pinfunction "PK4(ADC12/PCINT20)_85") (pintype "bidirectional"))
      (node (ref "TOP_HEADER1") (pin "16") (pinfunction "16_16") (pintype "passive"))
    )
    (net (code "46") (name "ADC13") (class "Default")
      (node (ref "IC2") (pin "84") (pinfunction "PK5(ADC13/PCINT21)_84") (pintype "bidirectional"))
      (node (ref "TOP_HEADER1") (pin "17") (pinfunction "17_17") (pintype "passive"))
    )
    (net (code "47") (name "ADC14") (class "Default")
      (node (ref "IC2") (pin "83") (pinfunction "PK6(ADC14/PCINT22)_83") (pintype "bidirectional"))
      (node (ref "TOP_HEADER1") (pin "18") (pinfunction "18_18") (pintype "passive"))
    )
    (net (code "48") (name "ADC15") (class "Default")
      (node (ref "IC2") (pin "82") (pinfunction "PK7(ADC15/PCINT23)_82") (pintype "bidirectional"))
      (node (ref "TOP_HEADER1") (pin "19") (pinfunction "19_19") (pintype "passive"))
    )
    (net (code "49") (name "AREF") (class "Default")
      (node (ref "IC2") (pin "98") (pinfunction "AREF_98") (pintype "bidirectional"))
    )
    (net (code "50") (name "BATT_IN") (class "Default")
      (node (ref "D2") (pin "A") (pinfunction "A_A") (pintype "passive"))
      (node (ref "D3") (pin "A") (pinfunction "A_A") (pintype "passive"))
      (node (ref "LEFT_HEADERS1") (pin "7") (pinfunction "7_7") (pintype "passive"))
      (node (ref "TOP_HEADER1") (pin "4") (pinfunction "4_4") (pintype "passive"))
    )
    (net (code "51") (name "D0_RX0") (class "Default")
      (node (ref "IC2") (pin "2") (pinfunction "(RXD0/PCIN8)PE0_2") (pintype "bidirectional"))
      (node (ref "LEFT_HEADERS1") (pin "1") (pinfunction "1_1") (pintype "passive"))
      (node (ref "U2") (pin "1") (pinfunction "TXD_1") (pintype "output"))
    )
    (net (code "52") (name "D1_TX0") (class "Default")
      (node (ref "IC2") (pin "3") (pinfunction "(TXD0)PE1_3") (pintype "bidirectional"))
      (node (ref "LEFT_HEADERS1") (pin "4") (pinfunction "4_4") (pintype "passive"))
      (node (ref "U2") (pin "5") (pinfunction "RXD_5") (pintype "input"))
    )
    (net (code "53") (name "D2") (class "Default")
      (node (ref "IC2") (pin "6") (pinfunction "(OC3B/INT4)PE4_6") (pintype "bidirectional"))
      (node (ref "JP2") (pin "1") (pinfunction "1_1") (pintype "passive"))
      (node (ref "LEFT_HEADERS1") (pin "6") (pinfunction "6_6") (pintype "passive"))
    )
    (net (code "54") (name "D3") (class "Default")
      (node (ref "IC2") (pin "7") (pinfunction "(OC3C/INT5)PE5_7") (pintype "bidirectional"))
      (node (ref "JP1") (pin "1") (pinfunction "1_1") (pintype "passive"))
      (node (ref "LEFT_HEADERS1") (pin "5") (pinfunction "5_5") (pintype "passive"))
    )
    (net (code "55") (name "D4") (class "Default")
      (node (ref "IC2") (pin "1") (pinfunction "(OC0B)PG5_1") (pintype "bidirectional"))
      (node (ref "LEFT_HEADERS1") (pin "2") (pinfunction "2_2") (pintype "passive"))
      (node (ref "R33") (pin "2") (pinfunction "2_2") (pintype "passive"))
      (node (ref "U10") (pin "G") (pinfunction "G_G") (pintype "passive"))
    )
    (net (code "56") (name "D5") (class "Default")
      (node (ref "IC2") (pin "5") (pinfunction "(OC3A/AIN1)PE3_5") (pintype "bidirectional"))
      (node (ref "LEFT_HEADERS1") (pin "3") (pinfunction "3_3") (pintype "passive"))
    )
    (net (code "57") (name "D6") (class "Default")
      (node (ref "IC2") (pin "15") (pinfunction "PH3(OC4A)_15") (pintype "bidirectional"))
      (node (ref "LEFT_HEADERS1") (pin "12") (pinfunction "12_12") (pintype "passive"))
    )
    (net (code "58") (name "D7") (class "Default")
      (node (ref "IC2") (pin "16") (pinfunction "PH4(OC4B)_16") (pintype "bidirectional"))
      (node (ref "LEFT_HEADERS1") (pin "11") (pinfunction "11_11") (pintype "passive"))
    )
    (net (code "59") (name "D8") (class "Default")
      (node (ref "IC2") (pin "17") (pinfunction "PH5(OC4C)_17") (pintype "bidirectional"))
      (node (ref "LEFT_HEADERS1") (pin "14") (pinfunction "14_14") (pintype "passive"))
    )
    (net (code "60") (name "D9") (class "Default")
      (node (ref "IC2") (pin "18") (pinfunction "PH6(OC2B)_18") (pintype "bidirectional"))
      (node (ref "LEFT_HEADERS1") (pin "13") (pinfunction "13_13") (pintype "passive"))
    )
    (net (code "61") (name "D10") (class "Default")
      (node (ref "IC2") (pin "23") (pinfunction "(OC2A/PCINT4)PB4_23") (pintype "bidirectional"))
      (node (ref "LEFT_HEADERS1") (pin "20") (pinfunction "20_20") (pintype "passive"))
    )
    (net (code "62") (name "D11") (class "Default")
      (node (ref "IC2") (pin "24") (pinfunction "(OC1A/PCINT5)PB5_24") (pintype "bidirectional"))
      (node (ref "LEFT_HEADERS1") (pin "19") (pinfunction "19_19") (pintype "passive"))
    )
    (net (code "63") (name "D12") (class "Default")
      (node (ref "IC2") (pin "25") (pinfunction "(OC1B/PCINT6)PB6_25") (pintype "bidirectional"))
    )
    (net (code "64") (name "D13") (class "Default")
      (node (ref "BOTTOM_HEADER1") (pin "2") (pinfunction "2_2") (pintype "passive"))
      (node (ref "IC2") (pin "26") (pinfunction "(OC0A/OC1C/PCINT7)PB7_26") (pintype "bidirectional"))
      (node (ref "R14") (pin "2") (pinfunction "2_2") (pintype "passive"))
    )
    (net (code "65") (name "D14_TX3") (class "Default")
      (node (ref "IC2") (pin "64") (pinfunction "PJ1(TXD3/PCINT10)_64") (pintype "bidirectional"))
      (node (ref "RIGHT_HEADERS1") (pin "7") (pinfunction "7_7") (pintype "passive"))
    )
    (net (code "66") (name "D15_RX3") (class "Default")
      (node (ref "IC2") (pin "63") (pinfunction "PJ0(RXD3/PCINT9)_63") (pintype "bidirectional"))
      (node (ref "RIGHT_HEADERS1") (pin "8") (pinfunction "8_8") (pintype "passive"))
    )
    (net (code "67") (name "D16_TX2") (class "Default")
      (node (ref "IC2") (pin "13") (pinfunction "PH1(TXD2)_13") (pintype "bidirectional"))
      (node (ref "LEFT_HEADERS1") (pin "9") (pinfunction "9_9") (pintype "passive"))
    )
    (net (code "68") (name "D17_RX2") (class "Default")
      (node (ref "IC2") (pin "12") (pinfunction "PH0(RXD2)_12") (pintype "bidirectional"))
      (node (ref "LEFT_HEADERS1") (pin "10") (pinfunction "10_10") (pintype "passive"))
    )
    (net (code "69") (name "D18_TX1") (class "Default")
      (node (ref "BOTTOM_HEADER1") (pin "15") (pinfunction "15_15") (pintype "passive"))
      (node (ref "U$61") (pin "3") (pinfunction "DIN_3") (pintype "input"))
    )
    (net (code "70") (name "D18_TXD1") (class "Default")
      (node (ref "IC2") (pin "46") (pinfunction "(TXD1/INT3)PD3_46") (pintype "bidirectional"))
    )
    (net (code "71") (name "D19_RX1") (class "Default")
      (node (ref "BOTTOM_HEADER1") (pin "16") (pinfunction "16_16") (pintype "passive"))
      (node (ref "IC2") (pin "45") (pinfunction "(RXD1/INT2)PD2_45") (pintype "bidirectional"))
      (node (ref "U$61") (pin "2") (pinfunction "DOUT_2") (pintype "output"))
    )
    (net (code "72") (name "D20_SDA") (class "Default")
      (node (ref "BOTTOM_HEADER1") (pin "13") (pinfunction "13_13") (pintype "passive"))
      (node (ref "IC2") (pin "44") (pinfunction "(SDA/INT1)PD1_44") (pintype "bidirectional"))
      (node (ref "IC7") (pin "5") (pinfunction "SDA_5") (pintype "bidirectional"))
      (node (ref "Q2") (pin "3") (pinfunction "D_3") (pintype "bidirectional"))
      (node (ref "Q6") (pin "3") (pinfunction "D_3") (pintype "bidirectional"))
      (node (ref "R19") (pin "2") (pinfunction "2_2") (pintype "passive"))
      (node (ref "R3") (pin "2") (pinfunction "2_2") (pintype "passive"))
      (node (ref "R37") (pin "1") (pinfunction "1_1") (pintype "passive"))
    )
    (net (code "73") (name "D21_SCL") (class "Default")
      (node (ref "BOTTOM_HEADER1") (pin "14") (pinfunction "14_14") (pintype "passive"))
      (node (ref "IC2") (pin "43") (pinfunction "(SCL/INT0)PD0_43") (pintype "bidirectional"))
      (node (ref "IC7") (pin "6") (pinfunction "SCL_6") (pintype "bidirectional"))
      (node (ref "Q1") (pin "3") (pinfunction "D_3") (pintype "bidirectional"))
      (node (ref "Q7") (pin "3") (pinfunction "D_3") (pintype "bidirectional"))
      (node (ref "R1") (pin "2") (pinfunction "2_2") (pintype "passive"))
      (node (ref "R20") (pin "1") (pinfunction "1_1") (pintype "passive"))
      (node (ref "R38") (pin "1") (pinfunction "1_1") (pintype "passive"))
    )
    (net (code "74") (name "D22") (class "Default")
      (node (ref "IC2") (pin "78") (pinfunction "(AD0)PA0_78") (pintype "bidirectional"))
      (node (ref "TOP_HEADER1") (pin "20") (pinfunction "20_20") (pintype "passive"))
    )
    (net (code "75") (name "D23") (class "Default")
      (node (ref "IC2") (pin "77") (pinfunction "(AD1)PA1_77") (pintype "bidirectional"))
    )
    (net (code "76") (name "D24") (class "Default")
      (node (ref "IC2") (pin "76") (pinfunction "(AD2)PA2_76") (pintype "bidirectional"))
    )
    (net (code "77") (name "D25") (class "Default")
      (node (ref "IC2") (pin "75") (pinfunction "(AD3)PA3_75") (pintype "bidirectional"))
      (node (ref "RIGHT_HEADERS1") (pin "1") (pinfunction "1_1") (pintype "passive"))
    )
    (net (code "78") (name "D26") (class "Default")
      (node (ref "IC2") (pin "74") (pinfunction "(AD4)PA4_74") (pintype "bidirectional"))
      (node (ref "RIGHT_HEADERS1") (pin "2") (pinfunction "2_2") (pintype "passive"))
    )
    (net (code "79") (name "D27") (class "Default")
      (node (ref "IC2") (pin "73") (pinfunction "(AD5)PA5_73") (pintype "bidirectional"))
      (node (ref "RIGHT_HEADERS1") (pin "3") (pinfunction "3_3") (pintype "passive"))
    )
    (net (code "80") (name "D28") (class "Default")
      (node (ref "IC2") (pin "72") (pinfunction "(AD6)PA6_72") (pintype "bidirectional"))
      (node (ref "R8") (pin "1") (pinfunction "1_1") (pintype "passive"))
      (node (ref "RIGHT_HEADERS1") (pin "4") (pinfunction "4_4") (pintype "passive"))
      (node (ref "X2") (pin "CD1") (pinfunction "CARD_DETECT_CD1") (pintype "passive"))
    )
    (net (code "81") (name "D29") (class "Default")
      (node (ref "IC2") (pin "71") (pinfunction "(AD7)PA7_71") (pintype "bidirectional"))
      (node (ref "RIGHT_HEADERS1") (pin "5") (pinfunction "5_5") (pintype "passive"))
    )
    (net (code "82") (name "D30") (class "Default")
      (node (ref "IC2") (pin "60") (pinfunction "(A15)PC7_60") (pintype "bidirectional"))
      (node (ref "RIGHT_HEADERS1") (pin "11") (pinfunction "11_11") (pintype "passive"))
    )
    (net (code "83") (name "D31") (class "Default")
      (node (ref "IC2") (pin "59") (pinfunction "(A14)PC6_59") (pintype "bidirectional"))
      (node (ref "RIGHT_HEADERS1") (pin "12") (pinfunction "12_12") (pintype "passive"))
    )
    (net (code "84") (name "D32") (class "Default")
      (node (ref "IC2") (pin "58") (pinfunction "(A13)PC5_58") (pintype "bidirectional"))
      (node (ref "RIGHT_HEADERS1") (pin "13") (pinfunction "13_13") (pintype "passive"))
    )
    (net (code "85") (name "D33") (class "Default")
      (node (ref "IC2") (pin "57") (pinfunction "(A12)PC4_57") (pintype "bidirectional"))
      (node (ref "RIGHT_HEADERS1") (pin "14") (pinfunction "14_14") (pintype "passive"))
    )
    (net (code "86") (name "D34") (class "Default")
      (node (ref "IC2") (pin "56") (pinfunction "(A11)PC3_56") (pintype "bidirectional"))
      (node (ref "RIGHT_HEADERS1") (pin "15") (pinfunction "15_15") (pintype "passive"))
    )
    (net (code "87") (name "D35") (class "Default")
      (node (ref "IC2") (pin "55") (pinfunction "(A10)PC2_55") (pintype "bidirectional"))
      (node (ref "RIGHT_HEADERS1") (pin "16") (pinfunction "16_16") (pintype "passive"))
    )
    (net (code "88") (name "D36") (class "Default")
      (node (ref "IC2") (pin "54") (pinfunction "(A9)PC1_54") (pintype "bidirectional"))
      (node (ref "RIGHT_HEADERS1") (pin "17") (pinfunction "17_17") (pintype "passive"))
    )
    (net (code "89") (name "D37") (class "Default")
      (node (ref "IC2") (pin "53") (pinfunction "(A8)PC0_53") (pintype "bidirectional"))
      (node (ref "RIGHT_HEADERS1") (pin "18") (pinfunction "18_18") (pintype "passive"))
    )
    (net (code "90") (name "D38") (class "Default")
      (node (ref "BOTTOM_HEADER1") (pin "18") (pinfunction "18_18") (pintype "passive"))
      (node (ref "IC2") (pin "50") (pinfunction "(T0)PD7_50") (pintype "bidirectional"))
    )
    (net (code "91") (name "D39") (class "Default")
      (node (ref "IC2") (pin "70") (pinfunction "(ALE)PG2_70") (pintype "bidirectional"))
      (node (ref "RIGHT_HEADERS1") (pin "6") (pinfunction "6_6") (pintype "passive"))
    )
    (net (code "92") (name "D40") (class "Default")
      (node (ref "IC2") (pin "52") (pinfunction "(RD)PG1_52") (pintype "bidirectional"))
      (node (ref "RIGHT_HEADERS1") (pin "19") (pinfunction "19_19") (pintype "passive"))
    )
    (net (code "93") (name "D41") (class "Default")
      (node (ref "IC2") (pin "51") (pinfunction "(WR)PG0_51") (pintype "bidirectional"))
      (node (ref "RIGHT_HEADERS1") (pin "20") (pinfunction "20_20") (pintype "passive"))
    )
    (net (code "94") (name "D42") (class "Default")
      (node (ref "BOTTOM_HEADER1") (pin "11") (pinfunction "11_11") (pintype "passive"))
      (node (ref "IC2") (pin "42") (pinfunction "PL7_42") (pintype "bidirectional"))
    )
    (net (code "95") (name "D43") (class "Default")
      (node (ref "BOTTOM_HEADER1") (pin "12") (pinfunction "12_12") (pintype "passive"))
      (node (ref "IC2") (pin "41") (pinfunction "PL6_41") (pintype "bidirectional"))
    )
    (net (code "96") (name "D44") (class "Default")
      (node (ref "BOTTOM_HEADER1") (pin "9") (pinfunction "9_9") (pintype "passive"))
      (node (ref "IC2") (pin "40") (pinfunction "PL5(OC5C)_40") (pintype "bidirectional"))
    )
    (net (code "97") (name "D45") (class "Default")
      (node (ref "BOTTOM_HEADER1") (pin "10") (pinfunction "10_10") (pintype "passive"))
      (node (ref "IC2") (pin "39") (pinfunction "PL4(OC5B)_39") (pintype "bidirectional"))
      (node (ref "SG2") (pin "+") (pinfunction "1_+") (pintype "passive"))
    )
    (net (code "98") (name "D46") (class "Default")
      (node (ref "BOTTOM_HEADER1") (pin "7") (pinfunction "7_7") (pintype "passive"))
      (node (ref "IC2") (pin "38") (pinfunction "PL3(OC5A)_38") (pintype "bidirectional"))
    )
    (net (code "99") (name "D47") (class "Default")
      (node (ref "BOTTOM_HEADER1") (pin "8") (pinfunction "8_8") (pintype "passive"))
      (node (ref "IC2") (pin "37") (pinfunction "PL2(T5)_37") (pintype "bidirectional"))
    )
    (net (code "100") (name "D48") (class "Default")
      (node (ref "BOTTOM_HEADER1") (pin "5") (pinfunction "5_5") (pintype "passive"))
      (node (ref "IC2") (pin "36") (pinfunction "PL1(ICP5)_36") (pintype "bidirectional"))
    )
    (net (code "101") (name "D49") (class "Default")
      (node (ref "BOTTOM_HEADER1") (pin "6") (pinfunction "6_6") (pintype "passive"))
      (node (ref "IC2") (pin "35") (pinfunction "PL0(ICP4)_35") (pintype "bidirectional"))
    )
    (net (code "102") (name "D50_MISO") (class "Default")
      (node (ref "IC2") (pin "22") (pinfunction "(MISO/PCINT3)PB3_22") (pintype "bidirectional"))
      (node (ref "ICSP1") (pin "1") (pinfunction "1_1") (pintype "bidirectional"))
      (node (ref "LEFT_HEADERS1") (pin "17") (pinfunction "17_17") (pintype "passive"))
      (node (ref "X2") (pin "7") (pinfunction "DATA_OUT_7") (pintype "output"))
    )
    (net (code "103") (name "D51_MOSI") (class "Default")
      (node (ref "IC2") (pin "21") (pinfunction "(MOSI/PCINT2)PB2_21") (pintype "bidirectional"))
      (node (ref "IC3") (pin "5") (pinfunction "I_5") (pintype "input"))
      (node (ref "ICSP1") (pin "4") (pinfunction "4_4") (pintype "bidirectional"))
      (node (ref "LEFT_HEADERS1") (pin "18") (pinfunction "18_18") (pintype "passive"))
    )
    (net (code "104") (name "D52_SCK") (class "Default")
      (node (ref "IC2") (pin "20") (pinfunction "(SCK/PCINT1)PB1_20") (pintype "bidirectional"))
      (node (ref "IC3") (pin "3") (pinfunction "I_3") (pintype "input"))
      (node (ref "IC3") (pin "9") (pinfunction "I_9") (pintype "input"))
      (node (ref "ICSP1") (pin "3") (pinfunction "3_3") (pintype "bidirectional"))
      (node (ref "LEFT_HEADERS1") (pin "15") (pinfunction "15_15") (pintype "passive"))
    )
    (net (code "105") (name "D53_SS") (class "Default")
      (node (ref "IC2") (pin "19") (pinfunction "(SS/PCINT0)PB0_19") (pintype "bidirectional"))
      (node (ref "IC3") (pin "7") (pinfunction "I_7") (pintype "input"))
      (node (ref "LEFT_HEADERS1") (pin "16") (pinfunction "16_16") (pintype "passive"))
    )
    (net (code "106") (name "GND") (class "Default")
      (node (ref "1") (pin "2") (pinfunction "2_2") (pintype "passive"))
      (node (ref "B2") (pin "-") (pinfunction "-_-") (pintype "passive"))
      (node (ref "BOTTOM_HEADER1") (pin "17") (pinfunction "17_17") (pintype "passive"))
      (node (ref "BOTTOM_HEADER1") (pin "19") (pinfunction "19_19") (pintype "passive"))
      (node (ref "BOTTOM_HEADER1") (pin "20") (pinfunction "20_20") (pintype "passive"))
      (node (ref "BOTTOM_HEADER1") (pin "3") (pinfunction "3_3") (pintype "passive"))
      (node (ref "C1") (pin "2") (pinfunction "P$2_2") (pintype "passive"))
      (node (ref "C10") (pin "2") (pinfunction "P$2_2") (pintype "passive"))
      (node (ref "C11") (pin "2") (pinfunction "P$2_2") (pintype "passive"))
      (node (ref "C12") (pin "2") (pinfunction "P$2_2") (pintype "passive"))
      (node (ref "C13") (pin "2") (pinfunction "P$2_2") (pintype "passive"))
      (node (ref "C14") (pin "2") (pinfunction "P$2_2") (pintype "passive"))
      (node (ref "C15") (pin "-") (pinfunction "-_-") (pintype "passive"))
      (node (ref "C16") (pin "-") (pinfunction "-_-") (pintype "passive"))
      (node (ref "C18") (pin "1") (pinfunction "P$1_1") (pintype "passive"))
      (node (ref "C19") (pin "1") (pinfunction "P$1_1") (pintype "passive"))
      (node (ref "C2") (pin "2") (pinfunction "P$2_2") (pintype "passive"))
      (node (ref "C20") (pin "2") (pinfunction "P$2_2") (pintype "passive"))
      (node (ref "C21") (pin "1") (pinfunction "P$1_1") (pintype "passive"))
      (node (ref "C22") (pin "2") (pinfunction "P$2_2") (pintype "passive"))
      (node (ref "C23") (pin "2") (pinfunction "P$2_2") (pintype "passive"))
      (node (ref "C24") (pin "2") (pinfunction "P$2_2") (pintype "passive"))
      (node (ref "C25") (pin "2") (pinfunction "P$2_2") (pintype "passive"))
      (node (ref "C26") (pin "2") (pinfunction "P$2_2") (pintype "passive"))
      (node (ref "C27") (pin "2") (pinfunction "P$2_2") (pintype "passive"))
      (node (ref "C28") (pin "2") (pinfunction "P$2_2") (pintype "passive"))
      (node (ref "C3") (pin "-") (pinfunction "-_-") (pintype "passive"))
      (node (ref "C31") (pin "2") (pinfunction "P$2_2") (pintype "passive"))
      (node (ref "C32") (pin "2") (pinfunction "P$2_2") (pintype "passive"))
      (node (ref "C33") (pin "2") (pinfunction "P$2_2") (pintype "passive"))
      (node (ref "C34") (pin "2") (pinfunction "P$2_2") (pintype "passive"))
      (node (ref "C4") (pin "2") (pinfunction "2_2") (pintype "passive"))
      (node (ref "C5") (pin "2") (pinfunction "P$2_2") (pintype "passive"))
      (node (ref "C6") (pin "2") (pinfunction "P$2_2") (pintype "passive"))
      (node (ref "C7") (pin "2") (pinfunction "P$2_2") (pintype "passive"))
      (node (ref "CN4") (pin "GND") (pinfunction "GND_GND") (pintype "power_in"))
      (node (ref "DROGUE3") (pin "1") (pinfunction "1_1") (pintype "passive"))
      (node (ref "IC1") (pin "P$3") (pinfunction "GND_P$3") (pintype "power_in"))
      (node (ref "IC2") (pin "11") (pinfunction "GND_11") (pintype "power_in"))
      (node (ref "IC2") (pin "32") (pinfunction "GND1_32") (pintype "power_in"))
      (node (ref "IC2") (pin "62") (pinfunction "GND2_62") (pintype "power_in"))
      (node (ref "IC2") (pin "81") (pinfunction "GND3_81") (pintype "power_in"))
      (node (ref "IC2") (pin "99") (pinfunction "AGND_99") (pintype "power_in"))
      (node (ref "IC3") (pin "11") (pinfunction "I_11") (pintype "input"))
      (node (ref "IC3") (pin "14") (pinfunction "I_14") (pintype "input"))
      (node (ref "IC3") (pin "8") (pinfunction "VSS_8") (pintype "power_in"))
      (node (ref "IC5") (pin "3") (pinfunction "GND_3") (pintype "passive"))
      (node (ref "IC6") (pin "2") (pinfunction "GND_2") (pintype "bidirectional"))
      (node (ref "IC7") (pin "4") (pinfunction "VSS_4") (pintype "power_in"))
      (node (ref "IC8") (pin "3") (pinfunction "GND_3") (pintype "passive"))
      (node (ref "IC9") (pin "14") (pinfunction "RESERVED(GND)_14") (pintype "power_in"))
      (node (ref "IC9") (pin "15") (pinfunction "RESERVED(GND)_15") (pintype "power_in"))
      (node (ref "IC9") (pin "16") (pinfunction "RESERVED(GND)_16") (pintype "power_in"))
      (node (ref "IC9") (pin "17") (pinfunction "RESERVED(GND)_17") (pintype "power_in"))
      (node (ref "IC9") (pin "18") (pinfunction "RESERVED(GND)_18") (pintype "power_in"))
      (node (ref "IC9") (pin "19") (pinfunction "GND_19") (pintype "power_in"))
      (node (ref "IC9") (pin "20") (pinfunction "GND_20") (pintype "power_in"))
      (node (ref "ICSP1") (pin "6") (pinfunction "6_6") (pintype "bidirectional"))
      (node (ref "J1") (pin "1") (pinfunction "1_1") (pintype "passive"))
      (node (ref "LED5") (pin "C") (pinfunction "C_C") (pintype "passive"))
      (node (ref "LED6") (pin "C") (pinfunction "C_C") (pintype "passive"))
      (node (ref "R33") (pin "1") (pinfunction "1_1") (pintype "passive"))
      (node (ref "R7") (pin "2") (pinfunction "2_2") (pintype "passive"))
      (node (ref "RIGHT_HEADERS1") (pin "9") (pinfunction "9_9") (pintype "passive"))
      (node (ref "S2") (pin "1") (pinfunction "1_1") (pintype "passive"))
      (node (ref "S2") (pin "2") (pinfunction "2_2") (pintype "passive"))
      (node (ref "TOP_HEADER1") (pin "2") (pinfunction "2_2") (pintype "passive"))
      (node (ref "U$1") (pin "P$1") (pinfunction "GND_P$1") (pintype "bidirectional"))
      (node (ref "U$1") (pin "P$2") (pinfunction "GND_P$2") (pintype "bidirectional"))
      (node (ref "U$6") (pin "2") (pinfunction "2_2") (pintype "passive"))
      (node (ref "U$61") (pin "10") (pinfunction "GND_10") (pintype "power_in"))
      (node (ref "U1") (pin "P$12") (pinfunction "GND_P$12") (pintype "bidirectional"))
      (node (ref "U1") (pin "P$19") (pinfunction "GND_P$19") (pintype "bidirectional"))
      (node (ref "U1") (pin "P$3") (pinfunction "GND_P$3") (pintype "bidirectional"))
      (node (ref "U1") (pin "P$8") (pinfunction "GND_P$8") (pintype "bidirectional"))
      (node (ref "U12") (pin "2") (pinfunction "GND_2") (pintype "power_in"))
      (node (ref "U2") (pin "18") (pinfunction "GND2_18") (pintype "power_in"))
      (node (ref "U2") (pin "21") (pinfunction "GND3_21") (pintype "power_in"))
      (node (ref "U2") (pin "25") (pinfunction "AGND_25") (pintype "power_in"))
      (node (ref "U2") (pin "7") (pinfunction "GND1_7") (pintype "power_in"))
      (node (ref "U3") (pin "2") (pinfunction "GND_2") (pintype "power_in"))
      (node (ref "U4") (pin "2") (pinfunction "GND_2") (pintype "power_in"))
      (node (ref "U6") (pin "1") (pinfunction "RSVRD(GND)_1") (pintype "bidirectional"))
      (node (ref "U6") (pin "3") (pinfunction "RSVRD(GND)_3") (pintype "bidirectional"))
      (node (ref "U6") (pin "6") (pinfunction "GND_6") (pintype "power_in"))
      (node (ref "U6") (pin "7") (pinfunction "GND_7") (pintype "power_in"))
      (node (ref "U7") (pin "2") (pinfunction "GND_2") (pintype "power_in"))
      (node (ref "X2") (pin "6") (pinfunction "VSS_6") (pintype "power_in"))
      (node (ref "X2") (pin "MT1") (pinfunction "GND_MT1") (pintype "power_in"))
      (node (ref "X2") (pin "MT2") (pinfunction "GND1_MT2") (pintype "power_in"))
    )
    (net (code "107") (name "GPS_RX") (class "Default")
      (node (ref "D5") (pin "C") (pinfunction "C_C") (pintype "passive"))
      (node (ref "JP2") (pin "2") (pinfunction "2_2") (pintype "passive"))
    )
    (net (code "108") (name "GPS_TX") (class "Default")
      (node (ref "JP1") (pin "2") (pinfunction "2_2") (pintype "passive"))
      (node (ref "U1") (pin "P$9") (pinfunction "TX_P$9") (pintype "bidirectional"))
    )
    (net (code "109") (name "IGNITER_BATT") (class "Default")
      (node (ref "J1") (pin "2") (pinfunction "2_2") (pintype "passive"))
      (node (ref "U10") (pin "D") (pinfunction "D_D") (pintype "passive"))
    )
    (net (code "110") (name "Net-(ACT1-PadC)") (class "Default")
      (node (ref "ACT1") (pin "C") (pinfunction "C_C") (pintype "passive"))
      (node (ref "R2") (pin "2") (pinfunction "2_2") (pintype "passive"))
    )
    (net (code "111") (name "Net-(C2-P$1)") (class "Default")
      (node (ref "C2") (pin "1") (pinfunction "P$1_1") (pintype "passive"))
      (node (ref "C6") (pin "1") (pinfunction "P$1_1") (pintype "passive"))
      (node (ref "FB2") (pin "2") (pinfunction "P$2_2") (pintype "bidirectional"))
      (node (ref "R5") (pin "2") (pinfunction "2_2") (pintype "passive"))
      (node (ref "U1") (pin "P$1") (pinfunction "VCC_P$1") (pintype "bidirectional"))
    )
    (net (code "112") (name "Net-(C5-P$1)") (class "Default")
      (node (ref "C5") (pin "1") (pinfunction "P$1_1") (pintype "passive"))
      (node (ref "R6") (pin "1") (pinfunction "1_1") (pintype "passive"))
      (node (ref "U3") (pin "3") (pinfunction "EN_3") (pintype "input"))
    )
    (net (code "113") (name "Net-(C7-P$1)") (class "Default")
      (node (ref "C7") (pin "1") (pinfunction "P$1_1") (pintype "passive"))
      (node (ref "IC7") (pin "8") (pinfunction "VDD_8") (pintype "power_in"))
      (node (ref "R4") (pin "2") (pinfunction "2_2") (pintype "passive"))
    )
    (net (code "114") (name "Net-(C10-P$1)") (class "Default")
      (node (ref "C10") (pin "1") (pinfunction "P$1_1") (pintype "passive"))
      (node (ref "IC1") (pin "P$2") (pinfunction "CAP_P$2") (pintype "passive"))
    )
    (net (code "115") (name "Net-(C17-P$1)") (class "Default")
      (node (ref "C17") (pin "1") (pinfunction "P$1_1") (pintype "passive"))
      (node (ref "U2") (pin "2") (pinfunction "DTR_2") (pintype "bidirectional"))
    )
    (net (code "116") (name "Net-(C33-P$1)") (class "Default")
      (node (ref "C33") (pin "1") (pinfunction "P$1_1") (pintype "passive"))
      (node (ref "IC9") (pin "24") (pinfunction "C1_24") (pintype "bidirectional"))
    )
    (net (code "117") (name "Net-(C34-P$1)") (class "Default")
      (node (ref "C34") (pin "1") (pinfunction "P$1_1") (pintype "passive"))
      (node (ref "IC9") (pin "21") (pinfunction "CAP_21") (pintype "bidirectional"))
    )
    (net (code "118") (name "Net-(DROGUE3-Pad2)") (class "Default")
      (node (ref "DROGUE3") (pin "2") (pinfunction "2_2") (pintype "passive"))
      (node (ref "U10") (pin "S") (pinfunction "S_S") (pintype "passive"))
    )
    (net (code "119") (name "Net-(FB2-P$1)") (class "Default")
      (node (ref "FB2") (pin "1") (pinfunction "P$1_1") (pintype "bidirectional"))
      (node (ref "U3") (pin "5") (pinfunction "OUT_5") (pintype "power_in"))
    )
    (net (code "120") (name "Net-(IC3A-O)") (class "Default")
      (node (ref "IC3") (pin "2") (pinfunction "O_2") (pintype "output"))
      (node (ref "X2") (pin "5") (pinfunction "SCLK_5") (pintype "input"))
    )
    (net (code "121") (name "Net-(IC3B-O)") (class "Default")
      (node (ref "IC3") (pin "4") (pinfunction "O_4") (pintype "output"))
      (node (ref "X2") (pin "3") (pinfunction "DATA_IN_3") (pintype "input"))
    )
    (net (code "122") (name "Net-(IC3C-O)") (class "Default")
      (node (ref "IC3") (pin "6") (pinfunction "O_6") (pintype "output"))
      (node (ref "R2") (pin "1") (pinfunction "1_1") (pintype "passive"))
      (node (ref "X2") (pin "2") (pinfunction "CS_2") (pintype "input"))
    )
    (net (code "123") (name "Net-(IC3D-O)") (class "Default")
      (node (ref "ACT1") (pin "A") (pinfunction "A_A") (pintype "passive"))
      (node (ref "IC3") (pin "10") (pinfunction "O_10") (pintype "output"))
    )
    (net (code "124") (name "Net-(IC7-XI)") (class "Default")
      (node (ref "IC7") (pin "1") (pinfunction "XI_1") (pintype "input"))
      (node (ref "Q4") (pin "P$1") (pinfunction "1_P$1") (pintype "passive"))
    )
    (net (code "125") (name "Net-(IC7-XO)") (class "Default")
      (node (ref "IC7") (pin "2") (pinfunction "XO_2") (pintype "output"))
      (node (ref "Q4") (pin "P$4") (pinfunction "2_P$4") (pintype "passive"))
    )
    (net (code "126") (name "Net-(IC8-VI)") (class "Default")
      (node (ref "D2") (pin "C") (pinfunction "C_C") (pintype "passive"))
      (node (ref "IC8") (pin "1") (pinfunction "VI_1") (pintype "input"))
    )
    (net (code "127") (name "Net-(IC8-VO)") (class "Default")
      (node (ref "IC8") (pin "2") (pinfunction "VO_2") (pintype "passive"))
      (node (ref "U$61") (pin "1") (pinfunction "VCC_1") (pintype "power_in"))
    )
    (net (code "128") (name "Net-(LED2-PadC)") (class "Default")
      (node (ref "LED2") (pin "C") (pinfunction "C_C") (pintype "passive"))
      (node (ref "R7") (pin "1") (pinfunction "1_1") (pintype "passive"))
    )
    (net (code "129") (name "Net-(LED5-PadA)") (class "Default")
      (node (ref "LED5") (pin "A") (pinfunction "A_A") (pintype "passive"))
      (node (ref "R13") (pin "1") (pinfunction "1_1") (pintype "passive"))
    )
    (net (code "130") (name "Net-(LED6-PadA)") (class "Default")
      (node (ref "LED6") (pin "A") (pinfunction "A_A") (pintype "passive"))
      (node (ref "R14") (pin "1") (pinfunction "1_1") (pintype "passive"))
    )
    (net (code "131") (name "Net-(LED7-PadC)") (class "Default")
      (node (ref "LED7") (pin "C") (pinfunction "C_C") (pintype "passive"))
      (node (ref "R17") (pin "1") (pinfunction "1_1") (pintype "passive"))
    )
    (net (code "132") (name "Net-(LED8-PadC)") (class "Default")
      (node (ref "LED8") (pin "C") (pinfunction "C_C") (pintype "passive"))
      (node (ref "R18") (pin "1") (pinfunction "1_1") (pintype "passive"))
    )
    (net (code "133") (name "Net-(R10-Pad1)") (class "Default")
      (node (ref "R10") (pin "1") (pinfunction "1_1") (pintype "passive"))
      (node (ref "R11") (pin "2") (pinfunction "2_2") (pintype "passive"))
      (node (ref "U$6") (pin "3") (pinfunction "3_3") (pintype "passive"))
    )
    (net (code "134") (name "Net-(SG2-2)") (class "Default")
      (node (ref "1") (pin "1") (pinfunction "1_1") (pintype "passive"))
      (node (ref "SG2") (pin "-") (pinfunction "2_-") (pintype "passive"))
    )
    (net (code "135") (name "Net-(U$1-SIGNAL)") (class "Default")
      (node (ref "U$1") (pin "P$3") (pinfunction "SIGNAL_P$3") (pintype "bidirectional"))
      (node (ref "U1") (pin "P$11") (pinfunction "EX_ANT_P$11") (pintype "bidirectional"))
    )
    (net (code "136") (name "Net-(U1-RX)") (class "Default")
      (node (ref "D5") (pin "A") (pinfunction "A_A") (pintype "passive"))
      (node (ref "R5") (pin "1") (pinfunction "1_1") (pintype "passive"))
      (node (ref "U1") (pin "P$10") (pinfunction "RX_P$10") (pintype "bidirectional"))
    )
    (net (code "137") (name "Net-(U2-RXLED)") (class "Default")
      (node (ref "R18") (pin "2") (pinfunction "2_2") (pintype "passive"))
      (node (ref "U2") (pin "22") (pinfunction "RXLED_22") (pintype "bidirectional"))
    )
    (net (code "138") (name "Net-(U2-TXLED)") (class "Default")
      (node (ref "R17") (pin "2") (pinfunction "2_2") (pintype "passive"))
      (node (ref "U2") (pin "23") (pinfunction "TXLED_23") (pintype "bidirectional"))
    )
    (net (code "139") (name "RESET") (class "Default")
      (node (ref "BOTTOM_HEADER1") (pin "1") (pinfunction "1_1") (pintype "passive"))
      (node (ref "C14") (pin "1") (pinfunction "P$1_1") (pintype "passive"))
      (node (ref "C17") (pin "2") (pinfunction "P$2_2") (pintype "passive"))
      (node (ref "IC2") (pin "30") (pinfunction "RESET_30") (pintype "input"))
      (node (ref "ICSP1") (pin "5") (pinfunction "5_5") (pintype "bidirectional"))
      (node (ref "R12") (pin "1") (pinfunction "1_1") (pintype "passive"))
      (node (ref "S2") (pin "3") (pinfunction "3_3") (pintype "passive"))
      (node (ref "S2") (pin "4") (pinfunction "4_4") (pintype "passive"))
    )
    (net (code "140") (name "SCL") (class "Default")
      (node (ref "R15") (pin "1") (pinfunction "1_1") (pintype "passive"))
    )
    (net (code "141") (name "SDA") (class "Default")
      (node (ref "R16") (pin "1") (pinfunction "1_1") (pintype "passive"))
    )
    (net (code "142") (name "VDD") (class "Default")
      (node (ref "C32") (pin "1") (pinfunction "P$1_1") (pintype "passive"))
      (node (ref "IC9") (pin "1") (pinfunction "VDDIO_1") (pintype "power_in"))
      (node (ref "IC9") (pin "22") (pinfunction "VDD_22") (pintype "power_in"))
      (node (ref "IC9") (pin "23") (pinfunction "VDD_23") (pintype "power_in"))
      (node (ref "IC9") (pin "3") (pinfunction "VDDIO_3") (pintype "power_in"))
      (node (ref "Q6") (pin "1") (pinfunction "G_1") (pintype "bidirectional"))
      (node (ref "Q7") (pin "1") (pinfunction "G_1") (pintype "bidirectional"))
      (node (ref "R35") (pin "2") (pinfunction "2_2") (pintype "passive"))
      (node (ref "R36") (pin "2") (pinfunction "2_2") (pintype "passive"))
      (node (ref "R39") (pin "2") (pinfunction "2_2") (pintype "passive"))
      (node (ref "R40") (pin "1") (pinfunction "1_1") (pintype "passive"))
      (node (ref "R41") (pin "1") (pinfunction "1_1") (pintype "passive"))
      (node (ref "R42") (pin "1") (pinfunction "1_1") (pintype "passive"))
      (node (ref "R43") (pin "1") (pinfunction "1_1") (pintype "passive"))
      (node (ref "U12") (pin "5") (pinfunction "OUT_5") (pintype "power_in"))
    )
    (net (code "143") (name "VIN") (class "Default")
      (node (ref "C15") (pin "+") (pinfunction "+_+") (pintype "passive"))
      (node (ref "D3") (pin "C") (pinfunction "C_C") (pintype "passive"))
      (node (ref "IC5") (pin "1") (pinfunction "VI_1") (pintype "input"))
    )
    (net (code "144") (name "VUSB") (class "Default")
      (node (ref "C19") (pin "2") (pinfunction "P$2_2") (pintype "passive"))
      (node (ref "C21") (pin "2") (pinfunction "P$2_2") (pintype "passive"))
      (node (ref "CN4") (pin "VBUS") (pinfunction "VBUS_VBUS") (pintype "power_in"))
      (node (ref "D4") (pin "A") (pinfunction "A_A") (pintype "passive"))
    )
    (net (code "145") (name "unconnected-(CN4-PadID)") (class "Default")
      (node (ref "CN4") (pin "ID") (pinfunction "ID_ID") (pintype "bidirectional"))
    )
    (net (code "146") (name "unconnected-(IC2-(CLKO{slash}ICP3{slash}INT7)PE7-Pad9)") (class "Default")
      (node (ref "IC2") (pin "9") (pinfunction "(CLKO/ICP3/INT7)PE7_9") (pintype "bidirectional"))
    )
    (net (code "147") (name "unconnected-(IC2-(ICP1)PD4-Pad47)") (class "Default")
      (node (ref "IC2") (pin "47") (pinfunction "(ICP1)PD4_47") (pintype "bidirectional"))
    )
    (net (code "148") (name "unconnected-(IC2-(T1)PD6-Pad49)") (class "Default")
      (node (ref "IC2") (pin "49") (pinfunction "(T1)PD6_49") (pintype "bidirectional"))
    )
    (net (code "149") (name "unconnected-(IC2-(T3{slash}INT6)PE6-Pad8)") (class "Default")
      (node (ref "IC2") (pin "8") (pinfunction "(T3/INT6)PE6_8") (pintype "bidirectional"))
    )
    (net (code "150") (name "unconnected-(IC2-(TOSC1)PG4-Pad29)") (class "Default")
      (node (ref "IC2") (pin "29") (pinfunction "(TOSC1)PG4_29") (pintype "bidirectional"))
    )
    (net (code "151") (name "unconnected-(IC2-(TOSC2)PG3-Pad28)") (class "Default")
      (node (ref "IC2") (pin "28") (pinfunction "(TOSC2)PG3_28") (pintype "bidirectional"))
    )
    (net (code "152") (name "unconnected-(IC2-(XCK0{slash}AIN0)PE2-Pad4)") (class "Default")
      (node (ref "IC2") (pin "4") (pinfunction "(XCK0/AIN0)PE2_4") (pintype "bidirectional"))
    )
    (net (code "153") (name "unconnected-(IC2-(XCK1)PD5-Pad48)") (class "Default")
      (node (ref "IC2") (pin "48") (pinfunction "(XCK1)PD5_48") (pintype "bidirectional"))
    )
    (net (code "154") (name "unconnected-(IC2-PH7(T4)-Pad27)") (class "Default")
      (node (ref "IC2") (pin "27") (pinfunction "PH7(T4)_27") (pintype "bidirectional"))
    )
    (net (code "155") (name "unconnected-(IC2-PJ2(XCK3{slash}PCINT11)-Pad65)") (class "Default")
      (node (ref "IC2") (pin "65") (pinfunction "PJ2(XCK3/PCINT11)_65") (pintype "bidirectional"))
    )
    (net (code "156") (name "unconnected-(IC2-PJ3(PCINT12)-Pad66)") (class "Default")
      (node (ref "IC2") (pin "66") (pinfunction "PJ3(PCINT12)_66") (pintype "bidirectional"))
    )
    (net (code "157") (name "unconnected-(IC2-PJ4(PCINT13)-Pad67)") (class "Default")
      (node (ref "IC2") (pin "67") (pinfunction "PJ4(PCINT13)_67") (pintype "bidirectional"))
    )
    (net (code "158") (name "unconnected-(IC2-PJ5(PCINT14)-Pad68)") (class "Default")
      (node (ref "IC2") (pin "68") (pinfunction "PJ5(PCINT14)_68") (pintype "bidirectional"))
    )
    (net (code "159") (name "unconnected-(IC2-PJ6(PCINT15)-Pad69)") (class "Default")
      (node (ref "IC2") (pin "69") (pinfunction "PJ6(PCINT15)_69") (pintype "bidirectional"))
    )
    (net (code "160") (name "unconnected-(IC2-PJ7-Pad79)") (class "Default")
      (node (ref "IC2") (pin "79") (pinfunction "PJ7_79") (pintype "bidirectional"))
    )
    (net (code "161") (name "unconnected-(IC3E-O-Pad12)") (class "Default")
      (node (ref "IC3") (pin "12") (pinfunction "O_12") (pintype "output"))
    )
    (net (code "162") (name "unconnected-(IC3F-O-Pad15)") (class "Default")
      (node (ref "IC3") (pin "15") (pinfunction "O_15") (pintype "output"))
    )
    (net (code "163") (name "unconnected-(IC6-BYP-Pad4)") (class "Default")
      (node (ref "IC6") (pin "4") (pinfunction "BYP_4") (pintype "bidirectional"))
    )
    (net (code "164") (name "unconnected-(IC7-~{INT1{slash}CLK}-Pad7)") (class "Default")
      (node (ref "IC7") (pin "7") (pinfunction "~{INT1/CLK}_7") (pintype "output"))
    )
    (net (code "165") (name "unconnected-(U$61-AD0{slash}DIO0-Pad20)") (class "Default")
      (node (ref "U$61") (pin "20") (pinfunction "AD0/DIO0_20") (pintype "bidirectional"))
    )
    (net (code "166") (name "unconnected-(U$61-AD1{slash}DIO1-Pad19)") (class "Default")
      (node (ref "U$61") (pin "19") (pinfunction "AD1/DIO1_19") (pintype "bidirectional"))
    )
    (net (code "167") (name "unconnected-(U$61-AD2{slash}DIO2-Pad18)") (class "Default")
      (node (ref "U$61") (pin "18") (pinfunction "AD2/DIO2_18") (pintype "bidirectional"))
    )
    (net (code "168") (name "unconnected-(U$61-AD3{slash}DIO3-Pad17)") (class "Default")
      (node (ref "U$61") (pin "17") (pinfunction "AD3/DIO3_17") (pintype "bidirectional"))
    )
    (net (code "169") (name "unconnected-(U$61-AD4{slash}DIO4-Pad11)") (class "Default")
      (node (ref "U$61") (pin "11") (pinfunction "AD4/DIO4_11") (pintype "bidirectional"))
    )
    (net (code "170") (name "unconnected-(U$61-ASC{slash}AD5{slash}DIO5-Pad15)") (class "Default")
      (node (ref "U$61") (pin "15") (pinfunction "ASC/AD5/DIO5_15") (pintype "bidirectional"))
    )
    (net (code "171") (name "unconnected-(U$61-CTS{slash}DIO7-Pad12)") (class "Default")
      (node (ref "U$61") (pin "12") (pinfunction "CTS/DIO7_12") (pintype "bidirectional"))
    )
    (net (code "172") (name "unconnected-(U$61-DO8-Pad4)") (class "Default")
      (node (ref "U$61") (pin "4") (pinfunction "DO8_4") (pintype "output"))
    )
    (net (code "173") (name "unconnected-(U$61-DTR{slash}DI8-Pad9)") (class "Default")
      (node (ref "U$61") (pin "9") (pinfunction "DTR/DI8_9") (pintype "input"))
    )
    (net (code "174") (name "unconnected-(U$61-ON{slash}SLEEP-Pad13)") (class "Default")
      (node (ref "U$61") (pin "13") (pinfunction "ON/SLEEP_13") (pintype "output"))
    )
    (net (code "175") (name "unconnected-(U$61-PWM0{slash}RSSI-Pad6)") (class "Default")
      (node (ref "U$61") (pin "6") (pinfunction "PWM0/RSSI_6") (pintype "output"))
    )
    (net (code "176") (name "unconnected-(U$61-PWM1-Pad7)") (class "Default")
      (node (ref "U$61") (pin "7") (pinfunction "PWM1_7") (pintype "output"))
    )
    (net (code "177") (name "unconnected-(U$61-RESERVED-Pad8)") (class "Default")
      (node (ref "U$61") (pin "8") (pinfunction "RESERVED_8") (pintype "no_connect"))
    )
    (net (code "178") (name "unconnected-(U$61-RESET-Pad5)") (class "Default")
      (node (ref "U$61") (pin "5") (pinfunction "RESET_5") (pintype "input"))
    )
    (net (code "179") (name "unconnected-(U$61-RTS{slash}AD6{slash}DIO6-Pad16)") (class "Default")
      (node (ref "U$61") (pin "16") (pinfunction "RTS/AD6/DIO6_16") (pintype "bidirectional"))
    )
    (net (code "180") (name "unconnected-(U$61-VREF-Pad14)") (class "Default")
      (node (ref "U$61") (pin "14") (pinfunction "VREF_14") (pintype "input"))
    )
    (net (code "181") (name "unconnected-(U1-NC-PadP$6)") (class "Default")
      (node (ref "U1") (pin "P$6") (pinfunction "NC_P$6") (pintype "bidirectional"))
    )
    (net (code "182") (name "unconnected-(U1-NC-PadP$7)") (class "Default")
      (node (ref "U1") (pin "P$7") (pinfunction "NC_P$7") (pintype "bidirectional"))
    )
    (net (code "183") (name "unconnected-(U1-NC-PadP$15)") (class "Default")
      (node (ref "U1") (pin "P$15") (pinfunction "NC_P$15") (pintype "bidirectional"))
    )
    (net (code "184") (name "unconnected-(U1-NC-PadP$16)") (class "Default")
      (node (ref "U1") (pin "P$16") (pinfunction "NC_P$16") (pintype "bidirectional"))
    )
    (net (code "185") (name "unconnected-(U1-NC-PadP$17)") (class "Default")
      (node (ref "U1") (pin "P$17") (pinfunction "NC_P$17") (pintype "bidirectional"))
    )
    (net (code "186") (name "unconnected-(U1-NC-PadP$18)") (class "Default")
      (node (ref "U1") (pin "P$18") (pinfunction "NC_P$18") (pintype "bidirectional"))
    )
    (net (code "187") (name "unconnected-(U1-NC-PadP$20)") (class "Default")
      (node (ref "U1") (pin "P$20") (pinfunction "NC_P$20") (pintype "bidirectional"))
    )
    (net (code "188") (name "unconnected-(U1-NRESET-PadP$2)") (class "Default")
      (node (ref "U1") (pin "P$2") (pinfunction "NRESET_P$2") (pintype "bidirectional"))
    )
    (net (code "189") (name "unconnected-(U1-RTCM-PadP$14)") (class "Default")
      (node (ref "U1") (pin "P$14") (pinfunction "RTCM_P$14") (pintype "bidirectional"))
    )
    (net (code "190") (name "unconnected-(U2-CTS-Pad11)") (class "Default")
      (node (ref "U2") (pin "11") (pinfunction "CTS_11") (pintype "bidirectional"))
    )
    (net (code "191") (name "unconnected-(U2-RTS-Pad3)") (class "Default")
      (node (ref "U2") (pin "3") (pinfunction "RTS_3") (pintype "bidirectional"))
    )
    (net (code "192") (name "unconnected-(U2-TEST-Pad26)") (class "Default")
      (node (ref "U2") (pin "26") (pinfunction "TEST_26") (pintype "input"))
    )
    (net (code "193") (name "unconnected-(U3-P4-Pad4)") (class "Default")
      (node (ref "U3") (pin "4") (pinfunction "P4_4") (pintype "bidirectional"))
    )
    (net (code "194") (name "unconnected-(U4-P4-Pad4)") (class "Default")
      (node (ref "U4") (pin "4") (pinfunction "P4_4") (pintype "bidirectional"))
    )
    (net (code "195") (name "unconnected-(U6-NC-Pad8)") (class "Default")
      (node (ref "U6") (pin "8") (pinfunction "NC_8") (pintype "no_connect"))
    )
    (net (code "196") (name "unconnected-(U6-NC-Pad9)") (class "Default")
      (node (ref "U6") (pin "9") (pinfunction "NC_9") (pintype "no_connect"))
    )
    (net (code "197") (name "unconnected-(U6-NC-Pad10)") (class "Default")
      (node (ref "U6") (pin "10") (pinfunction "NC_10") (pintype "no_connect"))
    )
    (net (code "198") (name "unconnected-(U6-NC-Pad11)") (class "Default")
      (node (ref "U6") (pin "11") (pinfunction "NC_11") (pintype "no_connect"))
    )
    (net (code "199") (name "unconnected-(U6-NC-Pad12)") (class "Default")
      (node (ref "U6") (pin "12") (pinfunction "NC_12") (pintype "no_connect"))
    )
    (net (code "200") (name "unconnected-(U6-NC-Pad13)") (class "Default")
      (node (ref "U6") (pin "13") (pinfunction "NC_13") (pintype "no_connect"))
    )
    (net (code "201") (name "unconnected-(U7-P4-Pad4)") (class "Default")
      (node (ref "U7") (pin "4") (pinfunction "P4_4") (pintype "bidirectional"))
    )
    (net (code "202") (name "unconnected-(U12-P4-Pad4)") (class "Default")
      (node (ref "U12") (pin "4") (pinfunction "P4_4") (pintype "bidirectional"))
    )
    (net (code "203") (name "unconnected-(X2-CARD_DETECT1-PadCD2)") (class "Default")
      (node (ref "X2") (pin "CD2") (pinfunction "CARD_DETECT1_CD2") (pintype "passive"))
    )
    (net (code "204") (name "unconnected-(X2-DAT1-Pad8)") (class "Default")
      (node (ref "X2") (pin "8") (pinfunction "DAT1_8") (pintype "bidirectional"))
    )
    (net (code "205") (name "unconnected-(X2-DAT2-Pad1)") (class "Default")
      (node (ref "X2") (pin "1") (pinfunction "DAT2_1") (pintype "bidirectional"))
    )
  )
)
